# 03_-_Keyboard_Matrix_1.net
KiCad netlist of a schematic drawn in Altium Designer
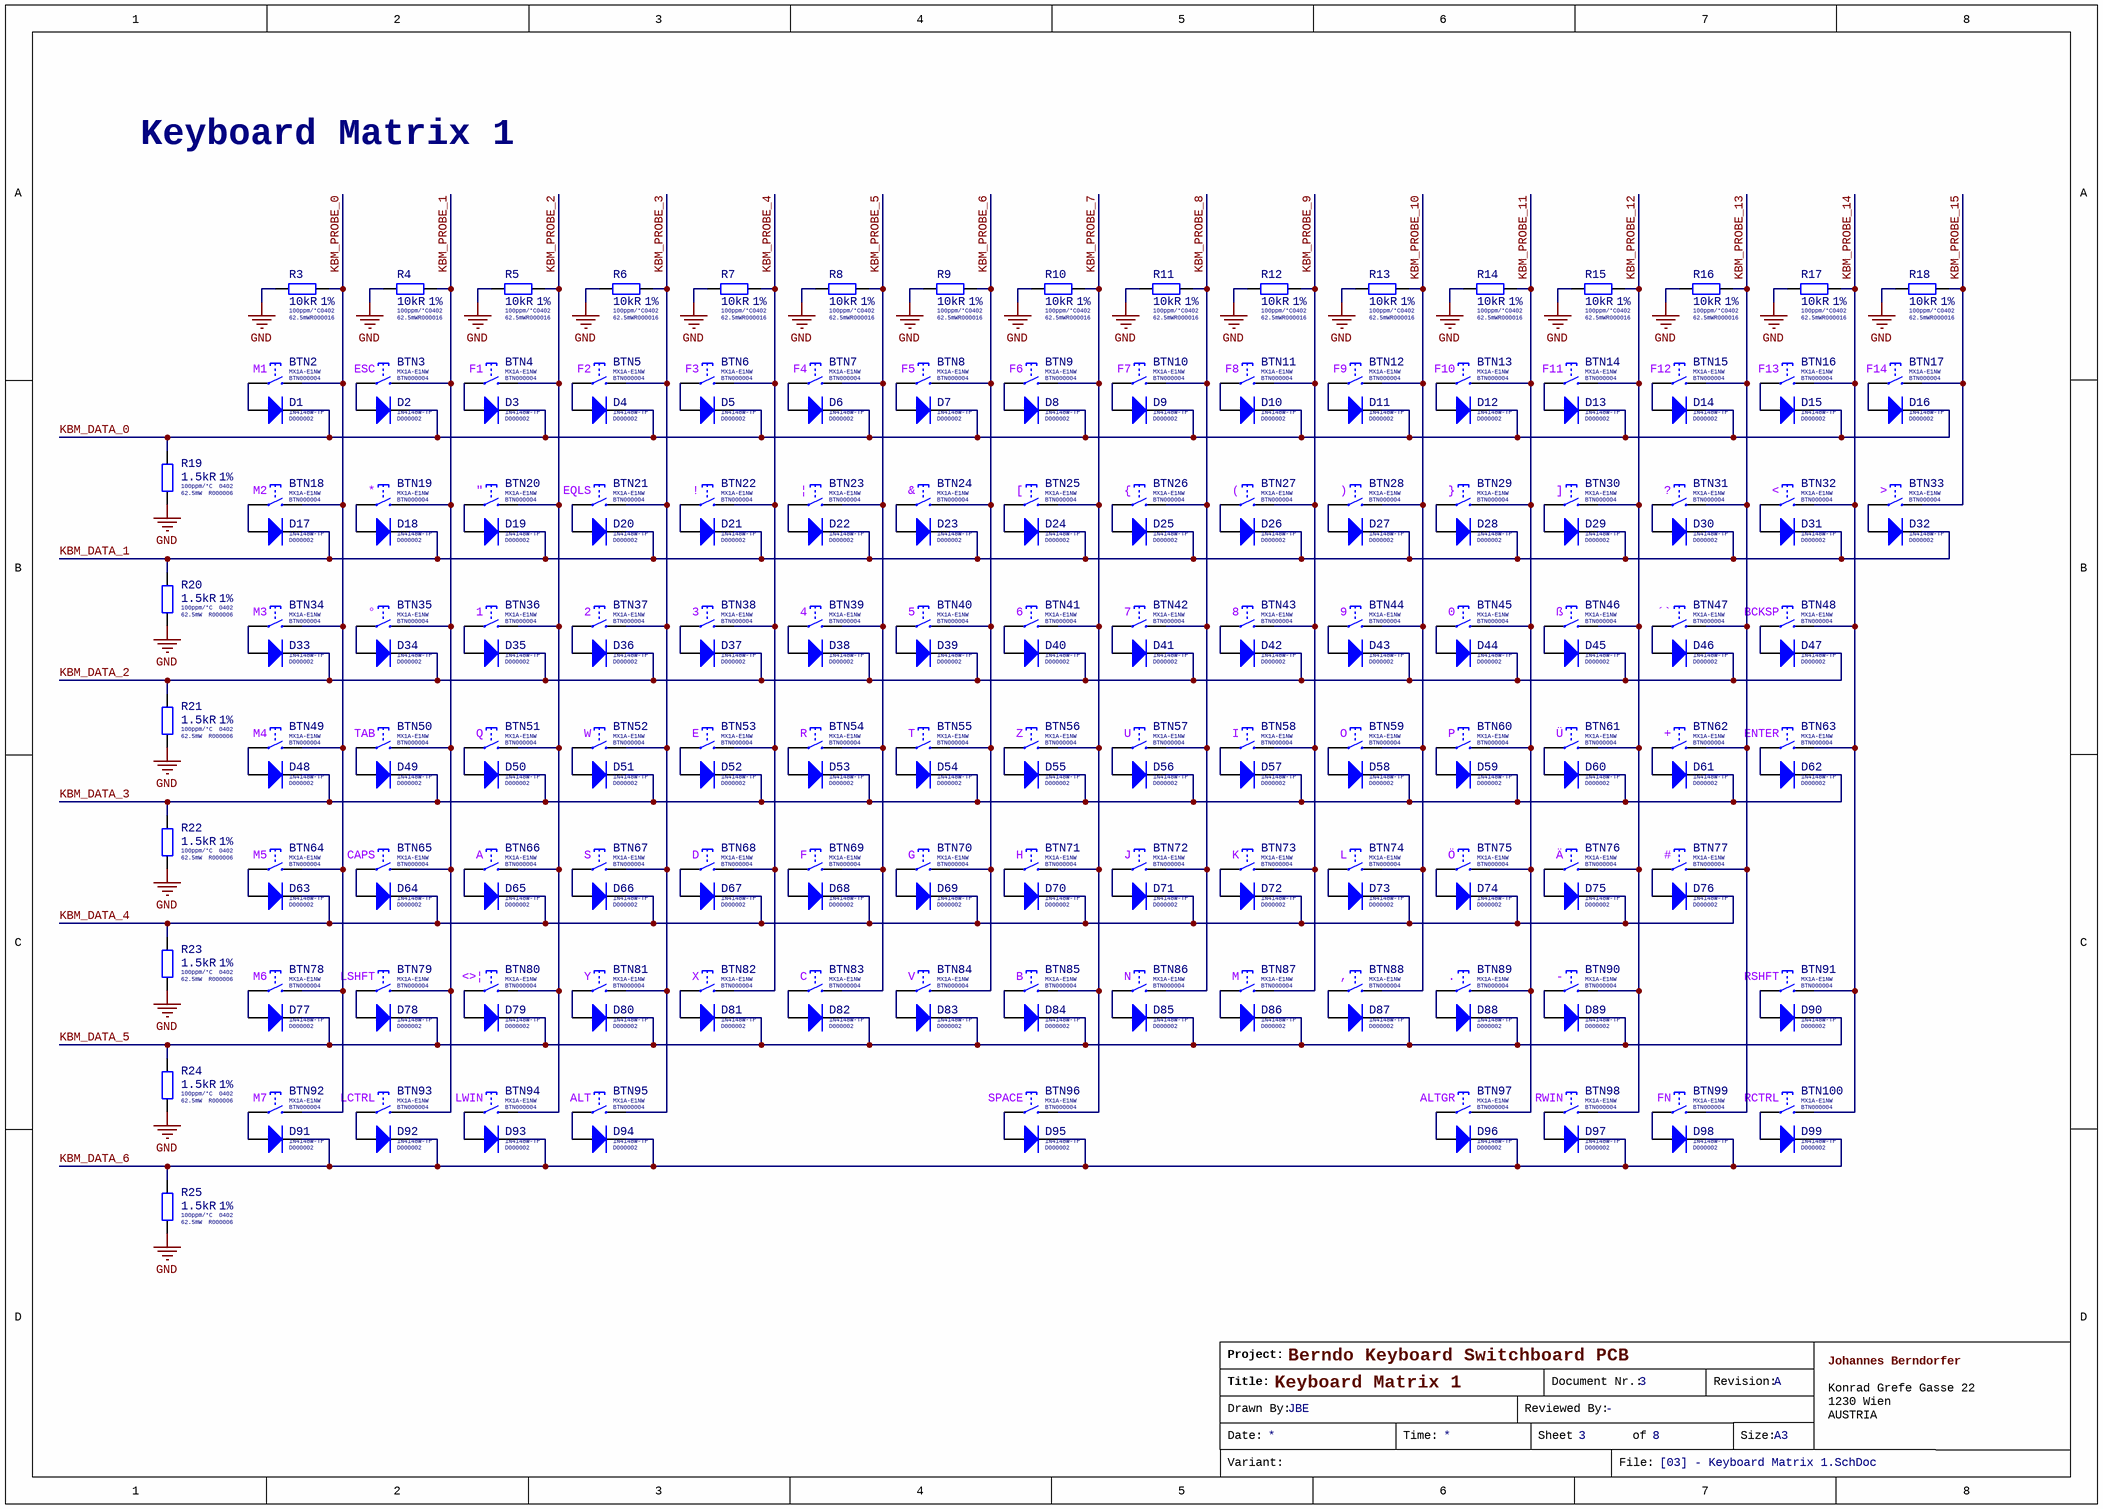
[diagram p0: [03] - Keyboard Matrix 1.SchDoc]

(export (version "E")
  (design (tool "Eeschema 10.0.6"))
  (components
    (comp (ref "BTN2")
      (value "MX1A-E1NW")
      (footprint "BTN-THT-MX-CHERRY")
      (description "BTN CHERRY MX BLUE SPST-NO 12V 10mA")
      (fields
        (field (name "MANUFACTURER") "Cherry")
        (field (name "INTERNAL PART NUMBER") "BTN000004")
        (field (name "KEY FUNCTION") "M1")
      )
      (libsource (lib "Altium_Lib_Standard") (part "MX1A-E1NW"))
    )
    (comp (ref "BTN3")
      (value "MX1A-E1NW")
      (footprint "BTN-THT-MX-CHERRY")
      (description "BTN CHERRY MX BLUE SPST-NO 12V 10mA")
      (fields
        (field (name "MANUFACTURER") "Cherry")
        (field (name "INTERNAL PART NUMBER") "BTN000004")
        (field (name "KEY FUNCTION") "ESC")
      )
      (libsource (lib "Altium_Lib_Standard") (part "MX1A-E1NW"))
    )
    (comp (ref "BTN4")
      (value "MX1A-E1NW")
      (footprint "BTN-THT-MX-CHERRY")
      (description "BTN CHERRY MX BLUE SPST-NO 12V 10mA")
      (fields
        (field (name "MANUFACTURER") "Cherry")
        (field (name "INTERNAL PART NUMBER") "BTN000004")
        (field (name "KEY FUNCTION") "F1")
      )
      (libsource (lib "Altium_Lib_Standard") (part "MX1A-E1NW"))
    )
    (comp (ref "BTN5")
      (value "MX1A-E1NW")
      (footprint "BTN-THT-MX-CHERRY")
      (description "BTN CHERRY MX BLUE SPST-NO 12V 10mA")
      (fields
        (field (name "MANUFACTURER") "Cherry")
        (field (name "INTERNAL PART NUMBER") "BTN000004")
        (field (name "KEY FUNCTION") "F2")
      )
      (libsource (lib "Altium_Lib_Standard") (part "MX1A-E1NW"))
    )
    (comp (ref "BTN6")
      (value "MX1A-E1NW")
      (footprint "BTN-THT-MX-CHERRY")
      (description "BTN CHERRY MX BLUE SPST-NO 12V 10mA")
      (fields
        (field (name "MANUFACTURER") "Cherry")
        (field (name "INTERNAL PART NUMBER") "BTN000004")
        (field (name "KEY FUNCTION") "F3")
      )
      (libsource (lib "Altium_Lib_Standard") (part "MX1A-E1NW"))
    )
    (comp (ref "BTN7")
      (value "MX1A-E1NW")
      (footprint "BTN-THT-MX-CHERRY")
      (description "BTN CHERRY MX BLUE SPST-NO 12V 10mA")
      (fields
        (field (name "MANUFACTURER") "Cherry")
        (field (name "INTERNAL PART NUMBER") "BTN000004")
        (field (name "KEY FUNCTION") "F4")
      )
      (libsource (lib "Altium_Lib_Standard") (part "MX1A-E1NW"))
    )
    (comp (ref "BTN8")
      (value "MX1A-E1NW")
      (footprint "BTN-THT-MX-CHERRY")
      (description "BTN CHERRY MX BLUE SPST-NO 12V 10mA")
      (fields
        (field (name "MANUFACTURER") "Cherry")
        (field (name "INTERNAL PART NUMBER") "BTN000004")
        (field (name "KEY FUNCTION") "F5")
      )
      (libsource (lib "Altium_Lib_Standard") (part "MX1A-E1NW"))
    )
    (comp (ref "BTN9")
      (value "MX1A-E1NW")
      (footprint "BTN-THT-MX-CHERRY")
      (description "BTN CHERRY MX BLUE SPST-NO 12V 10mA")
      (fields
        (field (name "MANUFACTURER") "Cherry")
        (field (name "INTERNAL PART NUMBER") "BTN000004")
        (field (name "KEY FUNCTION") "F6")
      )
      (libsource (lib "Altium_Lib_Standard") (part "MX1A-E1NW"))
    )
    (comp (ref "BTN10")
      (value "MX1A-E1NW")
      (footprint "BTN-THT-MX-CHERRY")
      (description "BTN CHERRY MX BLUE SPST-NO 12V 10mA")
      (fields
        (field (name "MANUFACTURER") "Cherry")
        (field (name "INTERNAL PART NUMBER") "BTN000004")
        (field (name "KEY FUNCTION") "F7")
      )
      (libsource (lib "Altium_Lib_Standard") (part "MX1A-E1NW"))
    )
    (comp (ref "BTN11")
      (value "MX1A-E1NW")
      (footprint "BTN-THT-MX-CHERRY")
      (description "BTN CHERRY MX BLUE SPST-NO 12V 10mA")
      (fields
        (field (name "MANUFACTURER") "Cherry")
        (field (name "INTERNAL PART NUMBER") "BTN000004")
        (field (name "KEY FUNCTION") "F8")
      )
      (libsource (lib "Altium_Lib_Standard") (part "MX1A-E1NW"))
    )
    (comp (ref "BTN12")
      (value "MX1A-E1NW")
      (footprint "BTN-THT-MX-CHERRY")
      (description "BTN CHERRY MX BLUE SPST-NO 12V 10mA")
      (fields
        (field (name "MANUFACTURER") "Cherry")
        (field (name "INTERNAL PART NUMBER") "BTN000004")
        (field (name "KEY FUNCTION") "F9")
      )
      (libsource (lib "Altium_Lib_Standard") (part "MX1A-E1NW"))
    )
    (comp (ref "BTN13")
      (value "MX1A-E1NW")
      (footprint "BTN-THT-MX-CHERRY")
      (description "BTN CHERRY MX BLUE SPST-NO 12V 10mA")
      (fields
        (field (name "MANUFACTURER") "Cherry")
        (field (name "INTERNAL PART NUMBER") "BTN000004")
        (field (name "KEY FUNCTION") "F10")
      )
      (libsource (lib "Altium_Lib_Standard") (part "MX1A-E1NW"))
    )
    (comp (ref "BTN14")
      (value "MX1A-E1NW")
      (footprint "BTN-THT-MX-CHERRY")
      (description "BTN CHERRY MX BLUE SPST-NO 12V 10mA")
      (fields
        (field (name "MANUFACTURER") "Cherry")
        (field (name "INTERNAL PART NUMBER") "BTN000004")
        (field (name "KEY FUNCTION") "F11")
      )
      (libsource (lib "Altium_Lib_Standard") (part "MX1A-E1NW"))
    )
    (comp (ref "BTN15")
      (value "MX1A-E1NW")
      (footprint "BTN-THT-MX-CHERRY")
      (description "BTN CHERRY MX BLUE SPST-NO 12V 10mA")
      (fields
        (field (name "MANUFACTURER") "Cherry")
        (field (name "INTERNAL PART NUMBER") "BTN000004")
        (field (name "KEY FUNCTION") "F12")
      )
      (libsource (lib "Altium_Lib_Standard") (part "MX1A-E1NW"))
    )
    (comp (ref "BTN16")
      (value "MX1A-E1NW")
      (footprint "BTN-THT-MX-CHERRY")
      (description "BTN CHERRY MX BLUE SPST-NO 12V 10mA")
      (fields
        (field (name "MANUFACTURER") "Cherry")
        (field (name "INTERNAL PART NUMBER") "BTN000004")
        (field (name "KEY FUNCTION") "F13")
      )
      (libsource (lib "Altium_Lib_Standard") (part "MX1A-E1NW"))
    )
    (comp (ref "BTN17")
      (value "MX1A-E1NW")
      (footprint "BTN-THT-MX-CHERRY")
      (description "BTN CHERRY MX BLUE SPST-NO 12V 10mA")
      (fields
        (field (name "MANUFACTURER") "Cherry")
        (field (name "INTERNAL PART NUMBER") "BTN000004")
        (field (name "KEY FUNCTION") "F14")
      )
      (libsource (lib "Altium_Lib_Standard") (part "MX1A-E1NW"))
    )
    (comp (ref "BTN18")
      (value "MX1A-E1NW")
      (footprint "BTN-THT-MX-CHERRY")
      (description "BTN CHERRY MX BLUE SPST-NO 12V 10mA")
      (fields
        (field (name "MANUFACTURER") "Cherry")
        (field (name "INTERNAL PART NUMBER") "BTN000004")
        (field (name "KEY FUNCTION") "M2")
      )
      (libsource (lib "Altium_Lib_Standard") (part "MX1A-E1NW"))
    )
    (comp (ref "BTN19")
      (value "MX1A-E1NW")
      (footprint "BTN-THT-MX-CHERRY")
      (description "BTN CHERRY MX BLUE SPST-NO 12V 10mA")
      (fields
        (field (name "MANUFACTURER") "Cherry")
        (field (name "INTERNAL PART NUMBER") "BTN000004")
        (field (name "KEY FUNCTION") "*")
      )
      (libsource (lib "Altium_Lib_Standard") (part "MX1A-E1NW"))
    )
    (comp (ref "BTN20")
      (value "MX1A-E1NW")
      (footprint "BTN-THT-MX-CHERRY")
      (description "BTN CHERRY MX BLUE SPST-NO 12V 10mA")
      (fields
        (field (name "MANUFACTURER") "Cherry")
        (field (name "INTERNAL PART NUMBER") "BTN000004")
        (field (name "KEY FUNCTION") "\"")
      )
      (libsource (lib "Altium_Lib_Standard") (part "MX1A-E1NW"))
    )
    (comp (ref "BTN21")
      (value "MX1A-E1NW")
      (footprint "BTN-THT-MX-CHERRY")
      (description "BTN CHERRY MX BLUE SPST-NO 12V 10mA")
      (fields
        (field (name "MANUFACTURER") "Cherry")
        (field (name "INTERNAL PART NUMBER") "BTN000004")
        (field (name "KEY FUNCTION") "EQLS")
      )
      (libsource (lib "Altium_Lib_Standard") (part "MX1A-E1NW"))
    )
    (comp (ref "BTN22")
      (value "MX1A-E1NW")
      (footprint "BTN-THT-MX-CHERRY")
      (description "BTN CHERRY MX BLUE SPST-NO 12V 10mA")
      (fields
        (field (name "MANUFACTURER") "Cherry")
        (field (name "INTERNAL PART NUMBER") "BTN000004")
        (field (name "KEY FUNCTION") "!")
      )
      (libsource (lib "Altium_Lib_Standard") (part "MX1A-E1NW"))
    )
    (comp (ref "BTN23")
      (value "MX1A-E1NW")
      (footprint "BTN-THT-MX-CHERRY")
      (description "BTN CHERRY MX BLUE SPST-NO 12V 10mA")
      (fields
        (field (name "MANUFACTURER") "Cherry")
        (field (name "INTERNAL PART NUMBER") "BTN000004")
        (field (name "KEY FUNCTION") "¦")
      )
      (libsource (lib "Altium_Lib_Standard") (part "MX1A-E1NW"))
    )
    (comp (ref "BTN24")
      (value "MX1A-E1NW")
      (footprint "BTN-THT-MX-CHERRY")
      (description "BTN CHERRY MX BLUE SPST-NO 12V 10mA")
      (fields
        (field (name "MANUFACTURER") "Cherry")
        (field (name "INTERNAL PART NUMBER") "BTN000004")
        (field (name "KEY FUNCTION") "&")
      )
      (libsource (lib "Altium_Lib_Standard") (part "MX1A-E1NW"))
    )
    (comp (ref "BTN25")
      (value "MX1A-E1NW")
      (footprint "BTN-THT-MX-CHERRY")
      (description "BTN CHERRY MX BLUE SPST-NO 12V 10mA")
      (fields
        (field (name "MANUFACTURER") "Cherry")
        (field (name "INTERNAL PART NUMBER") "BTN000004")
        (field (name "KEY FUNCTION") "[")
      )
      (libsource (lib "Altium_Lib_Standard") (part "MX1A-E1NW"))
    )
    (comp (ref "BTN26")
      (value "MX1A-E1NW")
      (footprint "BTN-THT-MX-CHERRY")
      (description "BTN CHERRY MX BLUE SPST-NO 12V 10mA")
      (fields
        (field (name "MANUFACTURER") "Cherry")
        (field (name "INTERNAL PART NUMBER") "BTN000004")
        (field (name "KEY FUNCTION") "{")
      )
      (libsource (lib "Altium_Lib_Standard") (part "MX1A-E1NW"))
    )
    (comp (ref "BTN27")
      (value "MX1A-E1NW")
      (footprint "BTN-THT-MX-CHERRY")
      (description "BTN CHERRY MX BLUE SPST-NO 12V 10mA")
      (fields
        (field (name "MANUFACTURER") "Cherry")
        (field (name "INTERNAL PART NUMBER") "BTN000004")
        (field (name "KEY FUNCTION") "(")
      )
      (libsource (lib "Altium_Lib_Standard") (part "MX1A-E1NW"))
    )
    (comp (ref "BTN28")
      (value "MX1A-E1NW")
      (footprint "BTN-THT-MX-CHERRY")
      (description "BTN CHERRY MX BLUE SPST-NO 12V 10mA")
      (fields
        (field (name "MANUFACTURER") "Cherry")
        (field (name "INTERNAL PART NUMBER") "BTN000004")
        (field (name "KEY FUNCTION") ")")
      )
      (libsource (lib "Altium_Lib_Standard") (part "MX1A-E1NW"))
    )
    (comp (ref "BTN29")
      (value "MX1A-E1NW")
      (footprint "BTN-THT-MX-CHERRY")
      (description "BTN CHERRY MX BLUE SPST-NO 12V 10mA")
      (fields
        (field (name "MANUFACTURER") "Cherry")
        (field (name "INTERNAL PART NUMBER") "BTN000004")
        (field (name "KEY FUNCTION") "}")
      )
      (libsource (lib "Altium_Lib_Standard") (part "MX1A-E1NW"))
    )
    (comp (ref "BTN30")
      (value "MX1A-E1NW")
      (footprint "BTN-THT-MX-CHERRY")
      (description "BTN CHERRY MX BLUE SPST-NO 12V 10mA")
      (fields
        (field (name "MANUFACTURER") "Cherry")
        (field (name "INTERNAL PART NUMBER") "BTN000004")
        (field (name "KEY FUNCTION") "]")
      )
      (libsource (lib "Altium_Lib_Standard") (part "MX1A-E1NW"))
    )
    (comp (ref "BTN31")
      (value "MX1A-E1NW")
      (footprint "BTN-THT-MX-CHERRY")
      (description "BTN CHERRY MX BLUE SPST-NO 12V 10mA")
      (fields
        (field (name "MANUFACTURER") "Cherry")
        (field (name "INTERNAL PART NUMBER") "BTN000004")
        (field (name "KEY FUNCTION") "?")
      )
      (libsource (lib "Altium_Lib_Standard") (part "MX1A-E1NW"))
    )
    (comp (ref "BTN32")
      (value "MX1A-E1NW")
      (footprint "BTN-THT-MX-CHERRY")
      (description "BTN CHERRY MX BLUE SPST-NO 12V 10mA")
      (fields
        (field (name "MANUFACTURER") "Cherry")
        (field (name "INTERNAL PART NUMBER") "BTN000004")
        (field (name "KEY FUNCTION") "<")
      )
      (libsource (lib "Altium_Lib_Standard") (part "MX1A-E1NW"))
    )
    (comp (ref "BTN33")
      (value "MX1A-E1NW")
      (footprint "BTN-THT-MX-CHERRY")
      (description "BTN CHERRY MX BLUE SPST-NO 12V 10mA")
      (fields
        (field (name "MANUFACTURER") "Cherry")
        (field (name "INTERNAL PART NUMBER") "BTN000004")
        (field (name "KEY FUNCTION") ">")
      )
      (libsource (lib "Altium_Lib_Standard") (part "MX1A-E1NW"))
    )
    (comp (ref "BTN34")
      (value "MX1A-E1NW")
      (footprint "BTN-THT-MX-CHERRY")
      (description "BTN CHERRY MX BLUE SPST-NO 12V 10mA")
      (fields
        (field (name "MANUFACTURER") "Cherry")
        (field (name "INTERNAL PART NUMBER") "BTN000004")
        (field (name "KEY FUNCTION") "M3")
      )
      (libsource (lib "Altium_Lib_Standard") (part "MX1A-E1NW"))
    )
    (comp (ref "BTN35")
      (value "MX1A-E1NW")
      (footprint "BTN-THT-MX-CHERRY")
      (description "BTN CHERRY MX BLUE SPST-NO 12V 10mA")
      (fields
        (field (name "MANUFACTURER") "Cherry")
        (field (name "INTERNAL PART NUMBER") "BTN000004")
        (field (name "KEY FUNCTION") "°")
      )
      (libsource (lib "Altium_Lib_Standard") (part "MX1A-E1NW"))
    )
    (comp (ref "BTN36")
      (value "MX1A-E1NW")
      (footprint "BTN-THT-MX-CHERRY")
      (description "BTN CHERRY MX BLUE SPST-NO 12V 10mA")
      (fields
        (field (name "MANUFACTURER") "Cherry")
        (field (name "INTERNAL PART NUMBER") "BTN000004")
        (field (name "KEY FUNCTION") "1")
      )
      (libsource (lib "Altium_Lib_Standard") (part "MX1A-E1NW"))
    )
    (comp (ref "BTN37")
      (value "MX1A-E1NW")
      (footprint "BTN-THT-MX-CHERRY")
      (description "BTN CHERRY MX BLUE SPST-NO 12V 10mA")
      (fields
        (field (name "MANUFACTURER") "Cherry")
        (field (name "INTERNAL PART NUMBER") "BTN000004")
        (field (name "KEY FUNCTION") "2")
      )
      (libsource (lib "Altium_Lib_Standard") (part "MX1A-E1NW"))
    )
    (comp (ref "BTN38")
      (value "MX1A-E1NW")
      (footprint "BTN-THT-MX-CHERRY")
      (description "BTN CHERRY MX BLUE SPST-NO 12V 10mA")
      (fields
        (field (name "MANUFACTURER") "Cherry")
        (field (name "INTERNAL PART NUMBER") "BTN000004")
        (field (name "KEY FUNCTION") "3")
      )
      (libsource (lib "Altium_Lib_Standard") (part "MX1A-E1NW"))
    )
    (comp (ref "BTN39")
      (value "MX1A-E1NW")
      (footprint "BTN-THT-MX-CHERRY")
      (description "BTN CHERRY MX BLUE SPST-NO 12V 10mA")
      (fields
        (field (name "MANUFACTURER") "Cherry")
        (field (name "INTERNAL PART NUMBER") "BTN000004")
        (field (name "KEY FUNCTION") "4")
      )
      (libsource (lib "Altium_Lib_Standard") (part "MX1A-E1NW"))
    )
    (comp (ref "BTN40")
      (value "MX1A-E1NW")
      (footprint "BTN-THT-MX-CHERRY")
      (description "BTN CHERRY MX BLUE SPST-NO 12V 10mA")
      (fields
        (field (name "MANUFACTURER") "Cherry")
        (field (name "INTERNAL PART NUMBER") "BTN000004")
        (field (name "KEY FUNCTION") "5")
      )
      (libsource (lib "Altium_Lib_Standard") (part "MX1A-E1NW"))
    )
    (comp (ref "BTN41")
      (value "MX1A-E1NW")
      (footprint "BTN-THT-MX-CHERRY")
      (description "BTN CHERRY MX BLUE SPST-NO 12V 10mA")
      (fields
        (field (name "MANUFACTURER") "Cherry")
        (field (name "INTERNAL PART NUMBER") "BTN000004")
        (field (name "KEY FUNCTION") "6")
      )
      (libsource (lib "Altium_Lib_Standard") (part "MX1A-E1NW"))
    )
    (comp (ref "BTN42")
      (value "MX1A-E1NW")
      (footprint "BTN-THT-MX-CHERRY")
      (description "BTN CHERRY MX BLUE SPST-NO 12V 10mA")
      (fields
        (field (name "MANUFACTURER") "Cherry")
        (field (name "INTERNAL PART NUMBER") "BTN000004")
        (field (name "KEY FUNCTION") "7")
      )
      (libsource (lib "Altium_Lib_Standard") (part "MX1A-E1NW"))
    )
    (comp (ref "BTN43")
      (value "MX1A-E1NW")
      (footprint "BTN-THT-MX-CHERRY")
      (description "BTN CHERRY MX BLUE SPST-NO 12V 10mA")
      (fields
        (field (name "MANUFACTURER") "Cherry")
        (field (name "INTERNAL PART NUMBER") "BTN000004")
        (field (name "KEY FUNCTION") "8")
      )
      (libsource (lib "Altium_Lib_Standard") (part "MX1A-E1NW"))
    )
    (comp (ref "BTN44")
      (value "MX1A-E1NW")
      (footprint "BTN-THT-MX-CHERRY")
      (description "BTN CHERRY MX BLUE SPST-NO 12V 10mA")
      (fields
        (field (name "MANUFACTURER") "Cherry")
        (field (name "INTERNAL PART NUMBER") "BTN000004")
        (field (name "KEY FUNCTION") "9")
      )
      (libsource (lib "Altium_Lib_Standard") (part "MX1A-E1NW"))
    )
    (comp (ref "BTN45")
      (value "MX1A-E1NW")
      (footprint "BTN-THT-MX-CHERRY")
      (description "BTN CHERRY MX BLUE SPST-NO 12V 10mA")
      (fields
        (field (name "MANUFACTURER") "Cherry")
        (field (name "INTERNAL PART NUMBER") "BTN000004")
        (field (name "KEY FUNCTION") "0")
      )
      (libsource (lib "Altium_Lib_Standard") (part "MX1A-E1NW"))
    )
    (comp (ref "BTN46")
      (value "MX1A-E1NW")
      (footprint "BTN-THT-MX-CHERRY")
      (description "BTN CHERRY MX BLUE SPST-NO 12V 10mA")
      (fields
        (field (name "MANUFACTURER") "Cherry")
        (field (name "INTERNAL PART NUMBER") "BTN000004")
        (field (name "KEY FUNCTION") "ß")
      )
      (libsource (lib "Altium_Lib_Standard") (part "MX1A-E1NW"))
    )
    (comp (ref "BTN47")
      (value "MX1A-E1NW")
      (footprint "BTN-THT-MX-CHERRY")
      (description "BTN CHERRY MX BLUE SPST-NO 12V 10mA")
      (fields
        (field (name "MANUFACTURER") "Cherry")
        (field (name "INTERNAL PART NUMBER") "BTN000004")
        (field (name "KEY FUNCTION") "´`")
      )
      (libsource (lib "Altium_Lib_Standard") (part "MX1A-E1NW"))
    )
    (comp (ref "BTN48")
      (value "MX1A-E1NW")
      (footprint "BTN-THT-MX-CHERRY")
      (description "BTN CHERRY MX BLUE SPST-NO 12V 10mA")
      (fields
        (field (name "MANUFACTURER") "Cherry")
        (field (name "INTERNAL PART NUMBER") "BTN000004")
        (field (name "KEY FUNCTION") "BCKSP")
      )
      (libsource (lib "Altium_Lib_Standard") (part "MX1A-E1NW"))
    )
    (comp (ref "BTN49")
      (value "MX1A-E1NW")
      (footprint "BTN-THT-MX-CHERRY")
      (description "BTN CHERRY MX BLUE SPST-NO 12V 10mA")
      (fields
        (field (name "MANUFACTURER") "Cherry")
        (field (name "INTERNAL PART NUMBER") "BTN000004")
        (field (name "KEY FUNCTION") "M4")
      )
      (libsource (lib "Altium_Lib_Standard") (part "MX1A-E1NW"))
    )
    (comp (ref "BTN50")
      (value "MX1A-E1NW")
      (footprint "BTN-THT-MX-CHERRY")
      (description "BTN CHERRY MX BLUE SPST-NO 12V 10mA")
      (fields
        (field (name "MANUFACTURER") "Cherry")
        (field (name "INTERNAL PART NUMBER") "BTN000004")
        (field (name "KEY FUNCTION") "TAB")
      )
      (libsource (lib "Altium_Lib_Standard") (part "MX1A-E1NW"))
    )
    (comp (ref "BTN51")
      (value "MX1A-E1NW")
      (footprint "BTN-THT-MX-CHERRY")
      (description "BTN CHERRY MX BLUE SPST-NO 12V 10mA")
      (fields
        (field (name "MANUFACTURER") "Cherry")
        (field (name "INTERNAL PART NUMBER") "BTN000004")
        (field (name "KEY FUNCTION") "Q")
      )
      (libsource (lib "Altium_Lib_Standard") (part "MX1A-E1NW"))
    )
    (comp (ref "BTN52")
      (value "MX1A-E1NW")
      (footprint "BTN-THT-MX-CHERRY")
      (description "BTN CHERRY MX BLUE SPST-NO 12V 10mA")
      (fields
        (field (name "MANUFACTURER") "Cherry")
        (field (name "INTERNAL PART NUMBER") "BTN000004")
        (field (name "KEY FUNCTION") "W")
      )
      (libsource (lib "Altium_Lib_Standard") (part "MX1A-E1NW"))
    )
    (comp (ref "BTN53")
      (value "MX1A-E1NW")
      (footprint "BTN-THT-MX-CHERRY")
      (description "BTN CHERRY MX BLUE SPST-NO 12V 10mA")
      (fields
        (field (name "MANUFACTURER") "Cherry")
        (field (name "INTERNAL PART NUMBER") "BTN000004")
        (field (name "KEY FUNCTION") "E")
      )
      (libsource (lib "Altium_Lib_Standard") (part "MX1A-E1NW"))
    )
    (comp (ref "BTN54")
      (value "MX1A-E1NW")
      (footprint "BTN-THT-MX-CHERRY")
      (description "BTN CHERRY MX BLUE SPST-NO 12V 10mA")
      (fields
        (field (name "MANUFACTURER") "Cherry")
        (field (name "INTERNAL PART NUMBER") "BTN000004")
        (field (name "KEY FUNCTION") "R")
      )
      (libsource (lib "Altium_Lib_Standard") (part "MX1A-E1NW"))
    )
    (comp (ref "BTN55")
      (value "MX1A-E1NW")
      (footprint "BTN-THT-MX-CHERRY")
      (description "BTN CHERRY MX BLUE SPST-NO 12V 10mA")
      (fields
        (field (name "MANUFACTURER") "Cherry")
        (field (name "INTERNAL PART NUMBER") "BTN000004")
        (field (name "KEY FUNCTION") "T")
      )
      (libsource (lib "Altium_Lib_Standard") (part "MX1A-E1NW"))
    )
    (comp (ref "BTN56")
      (value "MX1A-E1NW")
      (footprint "BTN-THT-MX-CHERRY")
      (description "BTN CHERRY MX BLUE SPST-NO 12V 10mA")
      (fields
        (field (name "MANUFACTURER") "Cherry")
        (field (name "INTERNAL PART NUMBER") "BTN000004")
        (field (name "KEY FUNCTION") "Z")
      )
      (libsource (lib "Altium_Lib_Standard") (part "MX1A-E1NW"))
    )
    (comp (ref "BTN57")
      (value "MX1A-E1NW")
      (footprint "BTN-THT-MX-CHERRY")
      (description "BTN CHERRY MX BLUE SPST-NO 12V 10mA")
      (fields
        (field (name "MANUFACTURER") "Cherry")
        (field (name "INTERNAL PART NUMBER") "BTN000004")
        (field (name "KEY FUNCTION") "U")
      )
      (libsource (lib "Altium_Lib_Standard") (part "MX1A-E1NW"))
    )
    (comp (ref "BTN58")
      (value "MX1A-E1NW")
      (footprint "BTN-THT-MX-CHERRY")
      (description "BTN CHERRY MX BLUE SPST-NO 12V 10mA")
      (fields
        (field (name "MANUFACTURER") "Cherry")
        (field (name "INTERNAL PART NUMBER") "BTN000004")
        (field (name "KEY FUNCTION") "I")
      )
      (libsource (lib "Altium_Lib_Standard") (part "MX1A-E1NW"))
    )
    (comp (ref "BTN59")
      (value "MX1A-E1NW")
      (footprint "BTN-THT-MX-CHERRY")
      (description "BTN CHERRY MX BLUE SPST-NO 12V 10mA")
      (fields
        (field (name "MANUFACTURER") "Cherry")
        (field (name "INTERNAL PART NUMBER") "BTN000004")
        (field (name "KEY FUNCTION") "O")
      )
      (libsource (lib "Altium_Lib_Standard") (part "MX1A-E1NW"))
    )
    (comp (ref "BTN60")
      (value "MX1A-E1NW")
      (footprint "BTN-THT-MX-CHERRY")
      (description "BTN CHERRY MX BLUE SPST-NO 12V 10mA")
      (fields
        (field (name "MANUFACTURER") "Cherry")
        (field (name "INTERNAL PART NUMBER") "BTN000004")
        (field (name "KEY FUNCTION") "P")
      )
      (libsource (lib "Altium_Lib_Standard") (part "MX1A-E1NW"))
    )
    (comp (ref "BTN61")
      (value "MX1A-E1NW")
      (footprint "BTN-THT-MX-CHERRY")
      (description "BTN CHERRY MX BLUE SPST-NO 12V 10mA")
      (fields
        (field (name "MANUFACTURER") "Cherry")
        (field (name "INTERNAL PART NUMBER") "BTN000004")
        (field (name "KEY FUNCTION") "Ü")
      )
      (libsource (lib "Altium_Lib_Standard") (part "MX1A-E1NW"))
    )
    (comp (ref "BTN62")
      (value "MX1A-E1NW")
      (footprint "BTN-THT-MX-CHERRY")
      (description "BTN CHERRY MX BLUE SPST-NO 12V 10mA")
      (fields
        (field (name "MANUFACTURER") "Cherry")
        (field (name "INTERNAL PART NUMBER") "BTN000004")
        (field (name "KEY FUNCTION") "+")
      )
      (libsource (lib "Altium_Lib_Standard") (part "MX1A-E1NW"))
    )
    (comp (ref "BTN63")
      (value "MX1A-E1NW")
      (footprint "BTN-THT-MX-CHERRY")
      (description "BTN CHERRY MX BLUE SPST-NO 12V 10mA")
      (fields
        (field (name "MANUFACTURER") "Cherry")
        (field (name "INTERNAL PART NUMBER") "BTN000004")
        (field (name "KEY FUNCTION") "ENTER")
      )
      (libsource (lib "Altium_Lib_Standard") (part "MX1A-E1NW"))
    )
    (comp (ref "BTN64")
      (value "MX1A-E1NW")
      (footprint "BTN-THT-MX-CHERRY")
      (description "BTN CHERRY MX BLUE SPST-NO 12V 10mA")
      (fields
        (field (name "MANUFACTURER") "Cherry")
        (field (name "INTERNAL PART NUMBER") "BTN000004")
        (field (name "KEY FUNCTION") "M5")
      )
      (libsource (lib "Altium_Lib_Standard") (part "MX1A-E1NW"))
    )
    (comp (ref "BTN65")
      (value "MX1A-E1NW")
      (footprint "BTN-THT-MX-CHERRY")
      (description "BTN CHERRY MX BLUE SPST-NO 12V 10mA")
      (fields
        (field (name "MANUFACTURER") "Cherry")
        (field (name "INTERNAL PART NUMBER") "BTN000004")
        (field (name "KEY FUNCTION") "CAPS")
      )
      (libsource (lib "Altium_Lib_Standard") (part "MX1A-E1NW"))
    )
    (comp (ref "BTN66")
      (value "MX1A-E1NW")
      (footprint "BTN-THT-MX-CHERRY")
      (description "BTN CHERRY MX BLUE SPST-NO 12V 10mA")
      (fields
        (field (name "MANUFACTURER") "Cherry")
        (field (name "INTERNAL PART NUMBER") "BTN000004")
        (field (name "KEY FUNCTION") "A")
      )
      (libsource (lib "Altium_Lib_Standard") (part "MX1A-E1NW"))
    )
    (comp (ref "BTN67")
      (value "MX1A-E1NW")
      (footprint "BTN-THT-MX-CHERRY")
      (description "BTN CHERRY MX BLUE SPST-NO 12V 10mA")
      (fields
        (field (name "MANUFACTURER") "Cherry")
        (field (name "INTERNAL PART NUMBER") "BTN000004")
        (field (name "KEY FUNCTION") "S")
      )
      (libsource (lib "Altium_Lib_Standard") (part "MX1A-E1NW"))
    )
    (comp (ref "BTN68")
      (value "MX1A-E1NW")
      (footprint "BTN-THT-MX-CHERRY")
      (description "BTN CHERRY MX BLUE SPST-NO 12V 10mA")
      (fields
        (field (name "MANUFACTURER") "Cherry")
        (field (name "INTERNAL PART NUMBER") "BTN000004")
        (field (name "KEY FUNCTION") "D")
      )
      (libsource (lib "Altium_Lib_Standard") (part "MX1A-E1NW"))
    )
    (comp (ref "BTN69")
      (value "MX1A-E1NW")
      (footprint "BTN-THT-MX-CHERRY")
      (description "BTN CHERRY MX BLUE SPST-NO 12V 10mA")
      (fields
        (field (name "MANUFACTURER") "Cherry")
        (field (name "INTERNAL PART NUMBER") "BTN000004")
        (field (name "KEY FUNCTION") "F")
      )
      (libsource (lib "Altium_Lib_Standard") (part "MX1A-E1NW"))
    )
    (comp (ref "BTN70")
      (value "MX1A-E1NW")
      (footprint "BTN-THT-MX-CHERRY")
      (description "BTN CHERRY MX BLUE SPST-NO 12V 10mA")
      (fields
        (field (name "MANUFACTURER") "Cherry")
        (field (name "INTERNAL PART NUMBER") "BTN000004")
        (field (name "KEY FUNCTION") "G")
      )
      (libsource (lib "Altium_Lib_Standard") (part "MX1A-E1NW"))
    )
    (comp (ref "BTN71")
      (value "MX1A-E1NW")
      (footprint "BTN-THT-MX-CHERRY")
      (description "BTN CHERRY MX BLUE SPST-NO 12V 10mA")
      (fields
        (field (name "MANUFACTURER") "Cherry")
        (field (name "INTERNAL PART NUMBER") "BTN000004")
        (field (name "KEY FUNCTION") "H")
      )
      (libsource (lib "Altium_Lib_Standard") (part "MX1A-E1NW"))
    )
    (comp (ref "BTN72")
      (value "MX1A-E1NW")
      (footprint "BTN-THT-MX-CHERRY")
      (description "BTN CHERRY MX BLUE SPST-NO 12V 10mA")
      (fields
        (field (name "MANUFACTURER") "Cherry")
        (field (name "INTERNAL PART NUMBER") "BTN000004")
        (field (name "KEY FUNCTION") "J")
      )
      (libsource (lib "Altium_Lib_Standard") (part "MX1A-E1NW"))
    )
    (comp (ref "BTN73")
      (value "MX1A-E1NW")
      (footprint "BTN-THT-MX-CHERRY")
      (description "BTN CHERRY MX BLUE SPST-NO 12V 10mA")
      (fields
        (field (name "MANUFACTURER") "Cherry")
        (field (name "INTERNAL PART NUMBER") "BTN000004")
        (field (name "KEY FUNCTION") "K")
      )
      (libsource (lib "Altium_Lib_Standard") (part "MX1A-E1NW"))
    )
    (comp (ref "BTN74")
      (value "MX1A-E1NW")
      (footprint "BTN-THT-MX-CHERRY")
      (description "BTN CHERRY MX BLUE SPST-NO 12V 10mA")
      (fields
        (field (name "MANUFACTURER") "Cherry")
        (field (name "INTERNAL PART NUMBER") "BTN000004")
        (field (name "KEY FUNCTION") "L")
      )
      (libsource (lib "Altium_Lib_Standard") (part "MX1A-E1NW"))
    )
    (comp (ref "BTN75")
      (value "MX1A-E1NW")
      (footprint "BTN-THT-MX-CHERRY")
      (description "BTN CHERRY MX BLUE SPST-NO 12V 10mA")
      (fields
        (field (name "MANUFACTURER") "Cherry")
        (field (name "INTERNAL PART NUMBER") "BTN000004")
        (field (name "KEY FUNCTION") "Ö")
      )
      (libsource (lib "Altium_Lib_Standard") (part "MX1A-E1NW"))
    )
    (comp (ref "BTN76")
      (value "MX1A-E1NW")
      (footprint "BTN-THT-MX-CHERRY")
      (description "BTN CHERRY MX BLUE SPST-NO 12V 10mA")
      (fields
        (field (name "MANUFACTURER") "Cherry")
        (field (name "INTERNAL PART NUMBER") "BTN000004")
        (field (name "KEY FUNCTION") "Ä")
      )
      (libsource (lib "Altium_Lib_Standard") (part "MX1A-E1NW"))
    )
    (comp (ref "BTN77")
      (value "MX1A-E1NW")
      (footprint "BTN-THT-MX-CHERRY")
      (description "BTN CHERRY MX BLUE SPST-NO 12V 10mA")
      (fields
        (field (name "MANUFACTURER") "Cherry")
        (field (name "INTERNAL PART NUMBER") "BTN000004")
        (field (name "KEY FUNCTION") "#")
      )
      (libsource (lib "Altium_Lib_Standard") (part "MX1A-E1NW"))
    )
    (comp (ref "BTN78")
      (value "MX1A-E1NW")
      (footprint "BTN-THT-MX-CHERRY")
      (description "BTN CHERRY MX BLUE SPST-NO 12V 10mA")
      (fields
        (field (name "MANUFACTURER") "Cherry")
        (field (name "INTERNAL PART NUMBER") "BTN000004")
        (field (name "KEY FUNCTION") "M6")
      )
      (libsource (lib "Altium_Lib_Standard") (part "MX1A-E1NW"))
    )
    (comp (ref "BTN79")
      (value "MX1A-E1NW")
      (footprint "BTN-THT-MX-CHERRY")
      (description "BTN CHERRY MX BLUE SPST-NO 12V 10mA")
      (fields
        (field (name "MANUFACTURER") "Cherry")
        (field (name "INTERNAL PART NUMBER") "BTN000004")
        (field (name "KEY FUNCTION") "LSHFT")
      )
      (libsource (lib "Altium_Lib_Standard") (part "MX1A-E1NW"))
    )
    (comp (ref "BTN80")
      (value "MX1A-E1NW")
      (footprint "BTN-THT-MX-CHERRY")
      (description "BTN CHERRY MX BLUE SPST-NO 12V 10mA")
      (fields
        (field (name "MANUFACTURER") "Cherry")
        (field (name "INTERNAL PART NUMBER") "BTN000004")
        (field (name "KEY FUNCTION") "<>¦")
      )
      (libsource (lib "Altium_Lib_Standard") (part "MX1A-E1NW"))
    )
    (comp (ref "BTN81")
      (value "MX1A-E1NW")
      (footprint "BTN-THT-MX-CHERRY")
      (description "BTN CHERRY MX BLUE SPST-NO 12V 10mA")
      (fields
        (field (name "MANUFACTURER") "Cherry")
        (field (name "INTERNAL PART NUMBER") "BTN000004")
        (field (name "KEY FUNCTION") "Y")
      )
      (libsource (lib "Altium_Lib_Standard") (part "MX1A-E1NW"))
    )
    (comp (ref "BTN82")
      (value "MX1A-E1NW")
      (footprint "BTN-THT-MX-CHERRY")
      (description "BTN CHERRY MX BLUE SPST-NO 12V 10mA")
      (fields
        (field (name "MANUFACTURER") "Cherry")
        (field (name "INTERNAL PART NUMBER") "BTN000004")
        (field (name "KEY FUNCTION") "X")
      )
      (libsource (lib "Altium_Lib_Standard") (part "MX1A-E1NW"))
    )
    (comp (ref "BTN83")
      (value "MX1A-E1NW")
      (footprint "BTN-THT-MX-CHERRY")
      (description "BTN CHERRY MX BLUE SPST-NO 12V 10mA")
      (fields
        (field (name "MANUFACTURER") "Cherry")
        (field (name "INTERNAL PART NUMBER") "BTN000004")
        (field (name "KEY FUNCTION") "C")
      )
      (libsource (lib "Altium_Lib_Standard") (part "MX1A-E1NW"))
    )
    (comp (ref "BTN84")
      (value "MX1A-E1NW")
      (footprint "BTN-THT-MX-CHERRY")
      (description "BTN CHERRY MX BLUE SPST-NO 12V 10mA")
      (fields
        (field (name "MANUFACTURER") "Cherry")
        (field (name "INTERNAL PART NUMBER") "BTN000004")
        (field (name "KEY FUNCTION") "V")
      )
      (libsource (lib "Altium_Lib_Standard") (part "MX1A-E1NW"))
    )
    (comp (ref "BTN85")
      (value "MX1A-E1NW")
      (footprint "BTN-THT-MX-CHERRY")
      (description "BTN CHERRY MX BLUE SPST-NO 12V 10mA")
      (fields
        (field (name "MANUFACTURER") "Cherry")
        (field (name "INTERNAL PART NUMBER") "BTN000004")
        (field (name "KEY FUNCTION") "B")
      )
      (libsource (lib "Altium_Lib_Standard") (part "MX1A-E1NW"))
    )
    (comp (ref "BTN86")
      (value "MX1A-E1NW")
      (footprint "BTN-THT-MX-CHERRY")
      (description "BTN CHERRY MX BLUE SPST-NO 12V 10mA")
      (fields
        (field (name "MANUFACTURER") "Cherry")
        (field (name "INTERNAL PART NUMBER") "BTN000004")
        (field (name "KEY FUNCTION") "N")
      )
      (libsource (lib "Altium_Lib_Standard") (part "MX1A-E1NW"))
    )
    (comp (ref "BTN87")
      (value "MX1A-E1NW")
      (footprint "BTN-THT-MX-CHERRY")
      (description "BTN CHERRY MX BLUE SPST-NO 12V 10mA")
      (fields
        (field (name "MANUFACTURER") "Cherry")
        (field (name "INTERNAL PART NUMBER") "BTN000004")
        (field (name "KEY FUNCTION") "M")
      )
      (libsource (lib "Altium_Lib_Standard") (part "MX1A-E1NW"))
    )
    (comp (ref "BTN88")
      (value "MX1A-E1NW")
      (footprint "BTN-THT-MX-CHERRY")
      (description "BTN CHERRY MX BLUE SPST-NO 12V 10mA")
      (fields
        (field (name "MANUFACTURER") "Cherry")
        (field (name "INTERNAL PART NUMBER") "BTN000004")
        (field (name "KEY FUNCTION") ",")
      )
      (libsource (lib "Altium_Lib_Standard") (part "MX1A-E1NW"))
    )
    (comp (ref "BTN89")
      (value "MX1A-E1NW")
      (footprint "BTN-THT-MX-CHERRY")
      (description "BTN CHERRY MX BLUE SPST-NO 12V 10mA")
      (fields
        (field (name "MANUFACTURER") "Cherry")
        (field (name "INTERNAL PART NUMBER") "BTN000004")
        (field (name "KEY FUNCTION") ".")
      )
      (libsource (lib "Altium_Lib_Standard") (part "MX1A-E1NW"))
    )
    (comp (ref "BTN90")
      (value "MX1A-E1NW")
      (footprint "BTN-THT-MX-CHERRY")
      (description "BTN CHERRY MX BLUE SPST-NO 12V 10mA")
      (fields
        (field (name "MANUFACTURER") "Cherry")
        (field (name "INTERNAL PART NUMBER") "BTN000004")
        (field (name "KEY FUNCTION") "-")
      )
      (libsource (lib "Altium_Lib_Standard") (part "MX1A-E1NW"))
    )
    (comp (ref "BTN91")
      (value "MX1A-E1NW")
      (footprint "BTN-THT-MX-CHERRY")
      (description "BTN CHERRY MX BLUE SPST-NO 12V 10mA")
      (fields
        (field (name "MANUFACTURER") "Cherry")
        (field (name "INTERNAL PART NUMBER") "BTN000004")
        (field (name "KEY FUNCTION") "RSHFT")
      )
      (libsource (lib "Altium_Lib_Standard") (part "MX1A-E1NW"))
    )
    (comp (ref "BTN92")
      (value "MX1A-E1NW")
      (footprint "BTN-THT-MX-CHERRY")
      (description "BTN CHERRY MX BLUE SPST-NO 12V 10mA")
      (fields
        (field (name "MANUFACTURER") "Cherry")
        (field (name "INTERNAL PART NUMBER") "BTN000004")
        (field (name "KEY FUNCTION") "M7")
      )
      (libsource (lib "Altium_Lib_Standard") (part "MX1A-E1NW"))
    )
    (comp (ref "BTN93")
      (value "MX1A-E1NW")
      (footprint "BTN-THT-MX-CHERRY")
      (description "BTN CHERRY MX BLUE SPST-NO 12V 10mA")
      (fields
        (field (name "MANUFACTURER") "Cherry")
        (field (name "INTERNAL PART NUMBER") "BTN000004")
        (field (name "KEY FUNCTION") "LCTRL")
      )
      (libsource (lib "Altium_Lib_Standard") (part "MX1A-E1NW"))
    )
    (comp (ref "BTN94")
      (value "MX1A-E1NW")
      (footprint "BTN-THT-MX-CHERRY")
      (description "BTN CHERRY MX BLUE SPST-NO 12V 10mA")
      (fields
        (field (name "MANUFACTURER") "Cherry")
        (field (name "INTERNAL PART NUMBER") "BTN000004")
        (field (name "KEY FUNCTION") "LWIN")
      )
      (libsource (lib "Altium_Lib_Standard") (part "MX1A-E1NW"))
    )
    (comp (ref "BTN95")
      (value "MX1A-E1NW")
      (footprint "BTN-THT-MX-CHERRY")
      (description "BTN CHERRY MX BLUE SPST-NO 12V 10mA")
      (fields
        (field (name "MANUFACTURER") "Cherry")
        (field (name "INTERNAL PART NUMBER") "BTN000004")
        (field (name "KEY FUNCTION") "ALT")
      )
      (libsource (lib "Altium_Lib_Standard") (part "MX1A-E1NW"))
    )
    (comp (ref "BTN96")
      (value "MX1A-E1NW")
      (footprint "BTN-THT-MX-CHERRY")
      (description "BTN CHERRY MX BLUE SPST-NO 12V 10mA")
      (fields
        (field (name "MANUFACTURER") "Cherry")
        (field (name "INTERNAL PART NUMBER") "BTN000004")
        (field (name "KEY FUNCTION") "SPACE")
      )
      (libsource (lib "Altium_Lib_Standard") (part "MX1A-E1NW"))
    )
    (comp (ref "BTN97")
      (value "MX1A-E1NW")
      (footprint "BTN-THT-MX-CHERRY")
      (description "BTN CHERRY MX BLUE SPST-NO 12V 10mA")
      (fields
        (field (name "MANUFACTURER") "Cherry")
        (field (name "INTERNAL PART NUMBER") "BTN000004")
        (field (name "KEY FUNCTION") "ALTGR")
      )
      (libsource (lib "Altium_Lib_Standard") (part "MX1A-E1NW"))
    )
    (comp (ref "BTN98")
      (value "MX1A-E1NW")
      (footprint "BTN-THT-MX-CHERRY")
      (description "BTN CHERRY MX BLUE SPST-NO 12V 10mA")
      (fields
        (field (name "MANUFACTURER") "Cherry")
        (field (name "INTERNAL PART NUMBER") "BTN000004")
        (field (name "KEY FUNCTION") "RWIN")
      )
      (libsource (lib "Altium_Lib_Standard") (part "MX1A-E1NW"))
    )
    (comp (ref "BTN99")
      (value "MX1A-E1NW")
      (footprint "BTN-THT-MX-CHERRY")
      (description "BTN CHERRY MX BLUE SPST-NO 12V 10mA")
      (fields
        (field (name "MANUFACTURER") "Cherry")
        (field (name "INTERNAL PART NUMBER") "BTN000004")
        (field (name "KEY FUNCTION") "FN")
      )
      (libsource (lib "Altium_Lib_Standard") (part "MX1A-E1NW"))
    )
    (comp (ref "BTN100")
      (value "MX1A-E1NW")
      (footprint "BTN-THT-MX-CHERRY")
      (description "BTN CHERRY MX BLUE SPST-NO 12V 10mA")
      (fields
        (field (name "MANUFACTURER") "Cherry")
        (field (name "INTERNAL PART NUMBER") "BTN000004")
        (field (name "KEY FUNCTION") "RCTRL")
      )
      (libsource (lib "Altium_Lib_Standard") (part "MX1A-E1NW"))
    )
    (comp (ref "D1")
      (value "1N4148W-TP")
      (footprint "D-SMD-SOD-123-MICRO-COMMERCIAL-COMPONENTS")
      (description "DIODE GEN-PURP 100V 150mA 1V25@150mA SMD SOD-23")
      (fields (field (name "MANUFACTURER") "MCC") (field (name "INTERNAL PART NUMBER") "D000002"))
      (libsource (lib "Altium_Lib_Standard") (part "1N4148W-TP"))
    )
    (comp (ref "D2")
      (value "1N4148W-TP")
      (footprint "D-SMD-SOD-123-MICRO-COMMERCIAL-COMPONENTS")
      (description "DIODE GEN-PURP 100V 150mA 1V25@150mA SMD SOD-23")
      (fields (field (name "MANUFACTURER") "MCC") (field (name "INTERNAL PART NUMBER") "D000002"))
      (libsource (lib "Altium_Lib_Standard") (part "1N4148W-TP"))
    )
    (comp (ref "D3")
      (value "1N4148W-TP")
      (footprint "D-SMD-SOD-123-MICRO-COMMERCIAL-COMPONENTS")
      (description "DIODE GEN-PURP 100V 150mA 1V25@150mA SMD SOD-23")
      (fields (field (name "MANUFACTURER") "MCC") (field (name "INTERNAL PART NUMBER") "D000002"))
      (libsource (lib "Altium_Lib_Standard") (part "1N4148W-TP"))
    )
    (comp (ref "D4")
      (value "1N4148W-TP")
      (footprint "D-SMD-SOD-123-MICRO-COMMERCIAL-COMPONENTS")
      (description "DIODE GEN-PURP 100V 150mA 1V25@150mA SMD SOD-23")
      (fields (field (name "MANUFACTURER") "MCC") (field (name "INTERNAL PART NUMBER") "D000002"))
      (libsource (lib "Altium_Lib_Standard") (part "1N4148W-TP"))
    )
    (comp (ref "D5")
      (value "1N4148W-TP")
      (footprint "D-SMD-SOD-123-MICRO-COMMERCIAL-COMPONENTS")
      (description "DIODE GEN-PURP 100V 150mA 1V25@150mA SMD SOD-23")
      (fields (field (name "MANUFACTURER") "MCC") (field (name "INTERNAL PART NUMBER") "D000002"))
      (libsource (lib "Altium_Lib_Standard") (part "1N4148W-TP"))
    )
    (comp (ref "D6")
      (value "1N4148W-TP")
      (footprint "D-SMD-SOD-123-MICRO-COMMERCIAL-COMPONENTS")
      (description "DIODE GEN-PURP 100V 150mA 1V25@150mA SMD SOD-23")
      (fields (field (name "MANUFACTURER") "MCC") (field (name "INTERNAL PART NUMBER") "D000002"))
      (libsource (lib "Altium_Lib_Standard") (part "1N4148W-TP"))
    )
    (comp (ref "D7")
      (value "1N4148W-TP")
      (footprint "D-SMD-SOD-123-MICRO-COMMERCIAL-COMPONENTS")
      (description "DIODE GEN-PURP 100V 150mA 1V25@150mA SMD SOD-23")
      (fields (field (name "MANUFACTURER") "MCC") (field (name "INTERNAL PART NUMBER") "D000002"))
      (libsource (lib "Altium_Lib_Standard") (part "1N4148W-TP"))
    )
    (comp (ref "D8")
      (value "1N4148W-TP")
      (footprint "D-SMD-SOD-123-MICRO-COMMERCIAL-COMPONENTS")
      (description "DIODE GEN-PURP 100V 150mA 1V25@150mA SMD SOD-23")
      (fields (field (name "MANUFACTURER") "MCC") (field (name "INTERNAL PART NUMBER") "D000002"))
      (libsource (lib "Altium_Lib_Standard") (part "1N4148W-TP"))
    )
    (comp (ref "D9")
      (value "1N4148W-TP")
      (footprint "D-SMD-SOD-123-MICRO-COMMERCIAL-COMPONENTS")
      (description "DIODE GEN-PURP 100V 150mA 1V25@150mA SMD SOD-23")
      (fields (field (name "MANUFACTURER") "MCC") (field (name "INTERNAL PART NUMBER") "D000002"))
      (libsource (lib "Altium_Lib_Standard") (part "1N4148W-TP"))
    )
    (comp (ref "D10")
      (value "1N4148W-TP")
      (footprint "D-SMD-SOD-123-MICRO-COMMERCIAL-COMPONENTS")
      (description "DIODE GEN-PURP 100V 150mA 1V25@150mA SMD SOD-23")
      (fields (field (name "MANUFACTURER") "MCC") (field (name "INTERNAL PART NUMBER") "D000002"))
      (libsource (lib "Altium_Lib_Standard") (part "1N4148W-TP"))
    )
    (comp (ref "D11")
      (value "1N4148W-TP")
      (footprint "D-SMD-SOD-123-MICRO-COMMERCIAL-COMPONENTS")
      (description "DIODE GEN-PURP 100V 150mA 1V25@150mA SMD SOD-23")
      (fields (field (name "MANUFACTURER") "MCC") (field (name "INTERNAL PART NUMBER") "D000002"))
      (libsource (lib "Altium_Lib_Standard") (part "1N4148W-TP"))
    )
    (comp (ref "D12")
      (value "1N4148W-TP")
      (footprint "D-SMD-SOD-123-MICRO-COMMERCIAL-COMPONENTS")
      (description "DIODE GEN-PURP 100V 150mA 1V25@150mA SMD SOD-23")
      (fields (field (name "MANUFACTURER") "MCC") (field (name "INTERNAL PART NUMBER") "D000002"))
      (libsource (lib "Altium_Lib_Standard") (part "1N4148W-TP"))
    )
    (comp (ref "D13")
      (value "1N4148W-TP")
      (footprint "D-SMD-SOD-123-MICRO-COMMERCIAL-COMPONENTS")
      (description "DIODE GEN-PURP 100V 150mA 1V25@150mA SMD SOD-23")
      (fields (field (name "MANUFACTURER") "MCC") (field (name "INTERNAL PART NUMBER") "D000002"))
      (libsource (lib "Altium_Lib_Standard") (part "1N4148W-TP"))
    )
    (comp (ref "D14")
      (value "1N4148W-TP")
      (footprint "D-SMD-SOD-123-MICRO-COMMERCIAL-COMPONENTS")
      (description "DIODE GEN-PURP 100V 150mA 1V25@150mA SMD SOD-23")
      (fields (field (name "MANUFACTURER") "MCC") (field (name "INTERNAL PART NUMBER") "D000002"))
      (libsource (lib "Altium_Lib_Standard") (part "1N4148W-TP"))
    )
    (comp (ref "D15")
      (value "1N4148W-TP")
      (footprint "D-SMD-SOD-123-MICRO-COMMERCIAL-COMPONENTS")
      (description "DIODE GEN-PURP 100V 150mA 1V25@150mA SMD SOD-23")
      (fields (field (name "MANUFACTURER") "MCC") (field (name "INTERNAL PART NUMBER") "D000002"))
      (libsource (lib "Altium_Lib_Standard") (part "1N4148W-TP"))
    )
    (comp (ref "D16")
      (value "1N4148W-TP")
      (footprint "D-SMD-SOD-123-MICRO-COMMERCIAL-COMPONENTS")
      (description "DIODE GEN-PURP 100V 150mA 1V25@150mA SMD SOD-23")
      (fields (field (name "MANUFACTURER") "MCC") (field (name "INTERNAL PART NUMBER") "D000002"))
      (libsource (lib "Altium_Lib_Standard") (part "1N4148W-TP"))
    )
    (comp (ref "D17")
      (value "1N4148W-TP")
      (footprint "D-SMD-SOD-123-MICRO-COMMERCIAL-COMPONENTS")
      (description "DIODE GEN-PURP 100V 150mA 1V25@150mA SMD SOD-23")
      (fields (field (name "MANUFACTURER") "MCC") (field (name "INTERNAL PART NUMBER") "D000002"))
      (libsource (lib "Altium_Lib_Standard") (part "1N4148W-TP"))
    )
    (comp (ref "D18")
      (value "1N4148W-TP")
      (footprint "D-SMD-SOD-123-MICRO-COMMERCIAL-COMPONENTS")
      (description "DIODE GEN-PURP 100V 150mA 1V25@150mA SMD SOD-23")
      (fields (field (name "MANUFACTURER") "MCC") (field (name "INTERNAL PART NUMBER") "D000002"))
      (libsource (lib "Altium_Lib_Standard") (part "1N4148W-TP"))
    )
    (comp (ref "D19")
      (value "1N4148W-TP")
      (footprint "D-SMD-SOD-123-MICRO-COMMERCIAL-COMPONENTS")
      (description "DIODE GEN-PURP 100V 150mA 1V25@150mA SMD SOD-23")
      (fields (field (name "MANUFACTURER") "MCC") (field (name "INTERNAL PART NUMBER") "D000002"))
      (libsource (lib "Altium_Lib_Standard") (part "1N4148W-TP"))
    )
    (comp (ref "D20")
      (value "1N4148W-TP")
      (footprint "D-SMD-SOD-123-MICRO-COMMERCIAL-COMPONENTS")
      (description "DIODE GEN-PURP 100V 150mA 1V25@150mA SMD SOD-23")
      (fields (field (name "MANUFACTURER") "MCC") (field (name "INTERNAL PART NUMBER") "D000002"))
      (libsource (lib "Altium_Lib_Standard") (part "1N4148W-TP"))
    )
    (comp (ref "D21")
      (value "1N4148W-TP")
      (footprint "D-SMD-SOD-123-MICRO-COMMERCIAL-COMPONENTS")
      (description "DIODE GEN-PURP 100V 150mA 1V25@150mA SMD SOD-23")
      (fields (field (name "MANUFACTURER") "MCC") (field (name "INTERNAL PART NUMBER") "D000002"))
      (libsource (lib "Altium_Lib_Standard") (part "1N4148W-TP"))
    )
    (comp (ref "D22")
      (value "1N4148W-TP")
      (footprint "D-SMD-SOD-123-MICRO-COMMERCIAL-COMPONENTS")
      (description "DIODE GEN-PURP 100V 150mA 1V25@150mA SMD SOD-23")
      (fields (field (name "MANUFACTURER") "MCC") (field (name "INTERNAL PART NUMBER") "D000002"))
      (libsource (lib "Altium_Lib_Standard") (part "1N4148W-TP"))
    )
    (comp (ref "D23")
      (value "1N4148W-TP")
      (footprint "D-SMD-SOD-123-MICRO-COMMERCIAL-COMPONENTS")
      (description "DIODE GEN-PURP 100V 150mA 1V25@150mA SMD SOD-23")
      (fields (field (name "MANUFACTURER") "MCC") (field (name "INTERNAL PART NUMBER") "D000002"))
      (libsource (lib "Altium_Lib_Standard") (part "1N4148W-TP"))
    )
    (comp (ref "D24")
      (value "1N4148W-TP")
      (footprint "D-SMD-SOD-123-MICRO-COMMERCIAL-COMPONENTS")
      (description "DIODE GEN-PURP 100V 150mA 1V25@150mA SMD SOD-23")
      (fields (field (name "MANUFACTURER") "MCC") (field (name "INTERNAL PART NUMBER") "D000002"))
      (libsource (lib "Altium_Lib_Standard") (part "1N4148W-TP"))
    )
    (comp (ref "D25")
      (value "1N4148W-TP")
      (footprint "D-SMD-SOD-123-MICRO-COMMERCIAL-COMPONENTS")
      (description "DIODE GEN-PURP 100V 150mA 1V25@150mA SMD SOD-23")
      (fields (field (name "MANUFACTURER") "MCC") (field (name "INTERNAL PART NUMBER") "D000002"))
      (libsource (lib "Altium_Lib_Standard") (part "1N4148W-TP"))
    )
    (comp (ref "D26")
      (value "1N4148W-TP")
      (footprint "D-SMD-SOD-123-MICRO-COMMERCIAL-COMPONENTS")
      (description "DIODE GEN-PURP 100V 150mA 1V25@150mA SMD SOD-23")
      (fields (field (name "MANUFACTURER") "MCC") (field (name "INTERNAL PART NUMBER") "D000002"))
      (libsource (lib "Altium_Lib_Standard") (part "1N4148W-TP"))
    )
    (comp (ref "D27")
      (value "1N4148W-TP")
      (footprint "D-SMD-SOD-123-MICRO-COMMERCIAL-COMPONENTS")
      (description "DIODE GEN-PURP 100V 150mA 1V25@150mA SMD SOD-23")
      (fields (field (name "MANUFACTURER") "MCC") (field (name "INTERNAL PART NUMBER") "D000002"))
      (libsource (lib "Altium_Lib_Standard") (part "1N4148W-TP"))
    )
    (comp (ref "D28")
      (value "1N4148W-TP")
      (footprint "D-SMD-SOD-123-MICRO-COMMERCIAL-COMPONENTS")
      (description "DIODE GEN-PURP 100V 150mA 1V25@150mA SMD SOD-23")
      (fields (field (name "MANUFACTURER") "MCC") (field (name "INTERNAL PART NUMBER") "D000002"))
      (libsource (lib "Altium_Lib_Standard") (part "1N4148W-TP"))
    )
    (comp (ref "D29")
      (value "1N4148W-TP")
      (footprint "D-SMD-SOD-123-MICRO-COMMERCIAL-COMPONENTS")
      (description "DIODE GEN-PURP 100V 150mA 1V25@150mA SMD SOD-23")
      (fields (field (name "MANUFACTURER") "MCC") (field (name "INTERNAL PART NUMBER") "D000002"))
      (libsource (lib "Altium_Lib_Standard") (part "1N4148W-TP"))
    )
    (comp (ref "D30")
      (value "1N4148W-TP")
      (footprint "D-SMD-SOD-123-MICRO-COMMERCIAL-COMPONENTS")
      (description "DIODE GEN-PURP 100V 150mA 1V25@150mA SMD SOD-23")
      (fields (field (name "MANUFACTURER") "MCC") (field (name "INTERNAL PART NUMBER") "D000002"))
      (libsource (lib "Altium_Lib_Standard") (part "1N4148W-TP"))
    )
    (comp (ref "D31")
      (value "1N4148W-TP")
      (footprint "D-SMD-SOD-123-MICRO-COMMERCIAL-COMPONENTS")
      (description "DIODE GEN-PURP 100V 150mA 1V25@150mA SMD SOD-23")
      (fields (field (name "MANUFACTURER") "MCC") (field (name "INTERNAL PART NUMBER") "D000002"))
      (libsource (lib "Altium_Lib_Standard") (part "1N4148W-TP"))
    )
    (comp (ref "D32")
      (value "1N4148W-TP")
      (footprint "D-SMD-SOD-123-MICRO-COMMERCIAL-COMPONENTS")
      (description "DIODE GEN-PURP 100V 150mA 1V25@150mA SMD SOD-23")
      (fields (field (name "MANUFACTURER") "MCC") (field (name "INTERNAL PART NUMBER") "D000002"))
      (libsource (lib "Altium_Lib_Standard") (part "1N4148W-TP"))
    )
    (comp (ref "D33")
      (value "1N4148W-TP")
      (footprint "D-SMD-SOD-123-MICRO-COMMERCIAL-COMPONENTS")
      (description "DIODE GEN-PURP 100V 150mA 1V25@150mA SMD SOD-23")
      (fields (field (name "MANUFACTURER") "MCC") (field (name "INTERNAL PART NUMBER") "D000002"))
      (libsource (lib "Altium_Lib_Standard") (part "1N4148W-TP"))
    )
    (comp (ref "D34")
      (value "1N4148W-TP")
      (footprint "D-SMD-SOD-123-MICRO-COMMERCIAL-COMPONENTS")
      (description "DIODE GEN-PURP 100V 150mA 1V25@150mA SMD SOD-23")
      (fields (field (name "MANUFACTURER") "MCC") (field (name "INTERNAL PART NUMBER") "D000002"))
      (libsource (lib "Altium_Lib_Standard") (part "1N4148W-TP"))
    )
    (comp (ref "D35")
      (value "1N4148W-TP")
      (footprint "D-SMD-SOD-123-MICRO-COMMERCIAL-COMPONENTS")
      (description "DIODE GEN-PURP 100V 150mA 1V25@150mA SMD SOD-23")
      (fields (field (name "MANUFACTURER") "MCC") (field (name "INTERNAL PART NUMBER") "D000002"))
      (libsource (lib "Altium_Lib_Standard") (part "1N4148W-TP"))
    )
    (comp (ref "D36")
      (value "1N4148W-TP")
      (footprint "D-SMD-SOD-123-MICRO-COMMERCIAL-COMPONENTS")
      (description "DIODE GEN-PURP 100V 150mA 1V25@150mA SMD SOD-23")
      (fields (field (name "MANUFACTURER") "MCC") (field (name "INTERNAL PART NUMBER") "D000002"))
      (libsource (lib "Altium_Lib_Standard") (part "1N4148W-TP"))
    )
    (comp (ref "D37")
      (value "1N4148W-TP")
      (footprint "D-SMD-SOD-123-MICRO-COMMERCIAL-COMPONENTS")
      (description "DIODE GEN-PURP 100V 150mA 1V25@150mA SMD SOD-23")
      (fields (field (name "MANUFACTURER") "MCC") (field (name "INTERNAL PART NUMBER") "D000002"))
      (libsource (lib "Altium_Lib_Standard") (part "1N4148W-TP"))
    )
    (comp (ref "D38")
      (value "1N4148W-TP")
      (footprint "D-SMD-SOD-123-MICRO-COMMERCIAL-COMPONENTS")
      (description "DIODE GEN-PURP 100V 150mA 1V25@150mA SMD SOD-23")
      (fields (field (name "MANUFACTURER") "MCC") (field (name "INTERNAL PART NUMBER") "D000002"))
      (libsource (lib "Altium_Lib_Standard") (part "1N4148W-TP"))
    )
    (comp (ref "D39")
      (value "1N4148W-TP")
      (footprint "D-SMD-SOD-123-MICRO-COMMERCIAL-COMPONENTS")
      (description "DIODE GEN-PURP 100V 150mA 1V25@150mA SMD SOD-23")
      (fields (field (name "MANUFACTURER") "MCC") (field (name "INTERNAL PART NUMBER") "D000002"))
      (libsource (lib "Altium_Lib_Standard") (part "1N4148W-TP"))
    )
    (comp (ref "D40")
      (value "1N4148W-TP")
      (footprint "D-SMD-SOD-123-MICRO-COMMERCIAL-COMPONENTS")
      (description "DIODE GEN-PURP 100V 150mA 1V25@150mA SMD SOD-23")
      (fields (field (name "MANUFACTURER") "MCC") (field (name "INTERNAL PART NUMBER") "D000002"))
      (libsource (lib "Altium_Lib_Standard") (part "1N4148W-TP"))
    )
    (comp (ref "D41")
      (value "1N4148W-TP")
      (footprint "D-SMD-SOD-123-MICRO-COMMERCIAL-COMPONENTS")
      (description "DIODE GEN-PURP 100V 150mA 1V25@150mA SMD SOD-23")
      (fields (field (name "MANUFACTURER") "MCC") (field (name "INTERNAL PART NUMBER") "D000002"))
      (libsource (lib "Altium_Lib_Standard") (part "1N4148W-TP"))
    )
    (comp (ref "D42")
      (value "1N4148W-TP")
      (footprint "D-SMD-SOD-123-MICRO-COMMERCIAL-COMPONENTS")
      (description "DIODE GEN-PURP 100V 150mA 1V25@150mA SMD SOD-23")
      (fields (field (name "MANUFACTURER") "MCC") (field (name "INTERNAL PART NUMBER") "D000002"))
      (libsource (lib "Altium_Lib_Standard") (part "1N4148W-TP"))
    )
    (comp (ref "D43")
      (value "1N4148W-TP")
      (footprint "D-SMD-SOD-123-MICRO-COMMERCIAL-COMPONENTS")
      (description "DIODE GEN-PURP 100V 150mA 1V25@150mA SMD SOD-23")
      (fields (field (name "MANUFACTURER") "MCC") (field (name "INTERNAL PART NUMBER") "D000002"))
      (libsource (lib "Altium_Lib_Standard") (part "1N4148W-TP"))
    )
    (comp (ref "D44")
      (value "1N4148W-TP")
      (footprint "D-SMD-SOD-123-MICRO-COMMERCIAL-COMPONENTS")
      (description "DIODE GEN-PURP 100V 150mA 1V25@150mA SMD SOD-23")
      (fields (field (name "MANUFACTURER") "MCC") (field (name "INTERNAL PART NUMBER") "D000002"))
      (libsource (lib "Altium_Lib_Standard") (part "1N4148W-TP"))
    )
    (comp (ref "D45")
      (value "1N4148W-TP")
      (footprint "D-SMD-SOD-123-MICRO-COMMERCIAL-COMPONENTS")
      (description "DIODE GEN-PURP 100V 150mA 1V25@150mA SMD SOD-23")
      (fields (field (name "MANUFACTURER") "MCC") (field (name "INTERNAL PART NUMBER") "D000002"))
      (libsource (lib "Altium_Lib_Standard") (part "1N4148W-TP"))
    )
    (comp (ref "D46")
      (value "1N4148W-TP")
      (footprint "D-SMD-SOD-123-MICRO-COMMERCIAL-COMPONENTS")
      (description "DIODE GEN-PURP 100V 150mA 1V25@150mA SMD SOD-23")
      (fields (field (name "MANUFACTURER") "MCC") (field (name "INTERNAL PART NUMBER") "D000002"))
      (libsource (lib "Altium_Lib_Standard") (part "1N4148W-TP"))
    )
    (comp (ref "D47")
      (value "1N4148W-TP")
      (footprint "D-SMD-SOD-123-MICRO-COMMERCIAL-COMPONENTS")
      (description "DIODE GEN-PURP 100V 150mA 1V25@150mA SMD SOD-23")
      (fields (field (name "MANUFACTURER") "MCC") (field (name "INTERNAL PART NUMBER") "D000002"))
      (libsource (lib "Altium_Lib_Standard") (part "1N4148W-TP"))
    )
    (comp (ref "D48")
      (value "1N4148W-TP")
      (footprint "D-SMD-SOD-123-MICRO-COMMERCIAL-COMPONENTS")
      (description "DIODE GEN-PURP 100V 150mA 1V25@150mA SMD SOD-23")
      (fields (field (name "MANUFACTURER") "MCC") (field (name "INTERNAL PART NUMBER") "D000002"))
      (libsource (lib "Altium_Lib_Standard") (part "1N4148W-TP"))
    )
    (comp (ref "D49")
      (value "1N4148W-TP")
      (footprint "D-SMD-SOD-123-MICRO-COMMERCIAL-COMPONENTS")
      (description "DIODE GEN-PURP 100V 150mA 1V25@150mA SMD SOD-23")
      (fields (field (name "MANUFACTURER") "MCC") (field (name "INTERNAL PART NUMBER") "D000002"))
      (libsource (lib "Altium_Lib_Standard") (part "1N4148W-TP"))
    )
    (comp (ref "D50")
      (value "1N4148W-TP")
      (footprint "D-SMD-SOD-123-MICRO-COMMERCIAL-COMPONENTS")
      (description "DIODE GEN-PURP 100V 150mA 1V25@150mA SMD SOD-23")
      (fields (field (name "MANUFACTURER") "MCC") (field (name "INTERNAL PART NUMBER") "D000002"))
      (libsource (lib "Altium_Lib_Standard") (part "1N4148W-TP"))
    )
    (comp (ref "D51")
      (value "1N4148W-TP")
      (footprint "D-SMD-SOD-123-MICRO-COMMERCIAL-COMPONENTS")
      (description "DIODE GEN-PURP 100V 150mA 1V25@150mA SMD SOD-23")
      (fields (field (name "MANUFACTURER") "MCC") (field (name "INTERNAL PART NUMBER") "D000002"))
      (libsource (lib "Altium_Lib_Standard") (part "1N4148W-TP"))
    )
    (comp (ref "D52")
      (value "1N4148W-TP")
      (footprint "D-SMD-SOD-123-MICRO-COMMERCIAL-COMPONENTS")
      (description "DIODE GEN-PURP 100V 150mA 1V25@150mA SMD SOD-23")
      (fields (field (name "MANUFACTURER") "MCC") (field (name "INTERNAL PART NUMBER") "D000002"))
      (libsource (lib "Altium_Lib_Standard") (part "1N4148W-TP"))
    )
    (comp (ref "D53")
      (value "1N4148W-TP")
      (footprint "D-SMD-SOD-123-MICRO-COMMERCIAL-COMPONENTS")
      (description "DIODE GEN-PURP 100V 150mA 1V25@150mA SMD SOD-23")
      (fields (field (name "MANUFACTURER") "MCC") (field (name "INTERNAL PART NUMBER") "D000002"))
      (libsource (lib "Altium_Lib_Standard") (part "1N4148W-TP"))
    )
    (comp (ref "D54")
      (value "1N4148W-TP")
      (footprint "D-SMD-SOD-123-MICRO-COMMERCIAL-COMPONENTS")
      (description "DIODE GEN-PURP 100V 150mA 1V25@150mA SMD SOD-23")
      (fields (field (name "MANUFACTURER") "MCC") (field (name "INTERNAL PART NUMBER") "D000002"))
      (libsource (lib "Altium_Lib_Standard") (part "1N4148W-TP"))
    )
    (comp (ref "D55")
      (value "1N4148W-TP")
      (footprint "D-SMD-SOD-123-MICRO-COMMERCIAL-COMPONENTS")
      (description "DIODE GEN-PURP 100V 150mA 1V25@150mA SMD SOD-23")
      (fields (field (name "MANUFACTURER") "MCC") (field (name "INTERNAL PART NUMBER") "D000002"))
      (libsource (lib "Altium_Lib_Standard") (part "1N4148W-TP"))
    )
    (comp (ref "D56")
      (value "1N4148W-TP")
      (footprint "D-SMD-SOD-123-MICRO-COMMERCIAL-COMPONENTS")
      (description "DIODE GEN-PURP 100V 150mA 1V25@150mA SMD SOD-23")
      (fields (field (name "MANUFACTURER") "MCC") (field (name "INTERNAL PART NUMBER") "D000002"))
      (libsource (lib "Altium_Lib_Standard") (part "1N4148W-TP"))
    )
    (comp (ref "D57")
      (value "1N4148W-TP")
      (footprint "D-SMD-SOD-123-MICRO-COMMERCIAL-COMPONENTS")
      (description "DIODE GEN-PURP 100V 150mA 1V25@150mA SMD SOD-23")
      (fields (field (name "MANUFACTURER") "MCC") (field (name "INTERNAL PART NUMBER") "D000002"))
      (libsource (lib "Altium_Lib_Standard") (part "1N4148W-TP"))
    )
    (comp (ref "D58")
      (value "1N4148W-TP")
      (footprint "D-SMD-SOD-123-MICRO-COMMERCIAL-COMPONENTS")
      (description "DIODE GEN-PURP 100V 150mA 1V25@150mA SMD SOD-23")
      (fields (field (name "MANUFACTURER") "MCC") (field (name "INTERNAL PART NUMBER") "D000002"))
      (libsource (lib "Altium_Lib_Standard") (part "1N4148W-TP"))
    )
    (comp (ref "D59")
      (value "1N4148W-TP")
      (footprint "D-SMD-SOD-123-MICRO-COMMERCIAL-COMPONENTS")
      (description "DIODE GEN-PURP 100V 150mA 1V25@150mA SMD SOD-23")
      (fields (field (name "MANUFACTURER") "MCC") (field (name "INTERNAL PART NUMBER") "D000002"))
      (libsource (lib "Altium_Lib_Standard") (part "1N4148W-TP"))
    )
    (comp (ref "D60")
      (value "1N4148W-TP")
      (footprint "D-SMD-SOD-123-MICRO-COMMERCIAL-COMPONENTS")
      (description "DIODE GEN-PURP 100V 150mA 1V25@150mA SMD SOD-23")
      (fields (field (name "MANUFACTURER") "MCC") (field (name "INTERNAL PART NUMBER") "D000002"))
      (libsource (lib "Altium_Lib_Standard") (part "1N4148W-TP"))
    )
    (comp (ref "D61")
      (value "1N4148W-TP")
      (footprint "D-SMD-SOD-123-MICRO-COMMERCIAL-COMPONENTS")
      (description "DIODE GEN-PURP 100V 150mA 1V25@150mA SMD SOD-23")
      (fields (field (name "MANUFACTURER") "MCC") (field (name "INTERNAL PART NUMBER") "D000002"))
      (libsource (lib "Altium_Lib_Standard") (part "1N4148W-TP"))
    )
    (comp (ref "D62")
      (value "1N4148W-TP")
      (footprint "D-SMD-SOD-123-MICRO-COMMERCIAL-COMPONENTS")
      (description "DIODE GEN-PURP 100V 150mA 1V25@150mA SMD SOD-23")
      (fields (field (name "MANUFACTURER") "MCC") (field (name "INTERNAL PART NUMBER") "D000002"))
      (libsource (lib "Altium_Lib_Standard") (part "1N4148W-TP"))
    )
    (comp (ref "D63")
      (value "1N4148W-TP")
      (footprint "D-SMD-SOD-123-MICRO-COMMERCIAL-COMPONENTS")
      (description "DIODE GEN-PURP 100V 150mA 1V25@150mA SMD SOD-23")
      (fields (field (name "MANUFACTURER") "MCC") (field (name "INTERNAL PART NUMBER") "D000002"))
      (libsource (lib "Altium_Lib_Standard") (part "1N4148W-TP"))
    )
    (comp (ref "D64")
      (value "1N4148W-TP")
      (footprint "D-SMD-SOD-123-MICRO-COMMERCIAL-COMPONENTS")
      (description "DIODE GEN-PURP 100V 150mA 1V25@150mA SMD SOD-23")
      (fields (field (name "MANUFACTURER") "MCC") (field (name "INTERNAL PART NUMBER") "D000002"))
      (libsource (lib "Altium_Lib_Standard") (part "1N4148W-TP"))
    )
    (comp (ref "D65")
      (value "1N4148W-TP")
      (footprint "D-SMD-SOD-123-MICRO-COMMERCIAL-COMPONENTS")
      (description "DIODE GEN-PURP 100V 150mA 1V25@150mA SMD SOD-23")
      (fields (field (name "MANUFACTURER") "MCC") (field (name "INTERNAL PART NUMBER") "D000002"))
      (libsource (lib "Altium_Lib_Standard") (part "1N4148W-TP"))
    )
    (comp (ref "D66")
      (value "1N4148W-TP")
      (footprint "D-SMD-SOD-123-MICRO-COMMERCIAL-COMPONENTS")
      (description "DIODE GEN-PURP 100V 150mA 1V25@150mA SMD SOD-23")
      (fields (field (name "MANUFACTURER") "MCC") (field (name "INTERNAL PART NUMBER") "D000002"))
      (libsource (lib "Altium_Lib_Standard") (part "1N4148W-TP"))
    )
    (comp (ref "D67")
      (value "1N4148W-TP")
      (footprint "D-SMD-SOD-123-MICRO-COMMERCIAL-COMPONENTS")
      (description "DIODE GEN-PURP 100V 150mA 1V25@150mA SMD SOD-23")
      (fields (field (name "MANUFACTURER") "MCC") (field (name "INTERNAL PART NUMBER") "D000002"))
      (libsource (lib "Altium_Lib_Standard") (part "1N4148W-TP"))
    )
    (comp (ref "D68")
      (value "1N4148W-TP")
      (footprint "D-SMD-SOD-123-MICRO-COMMERCIAL-COMPONENTS")
      (description "DIODE GEN-PURP 100V 150mA 1V25@150mA SMD SOD-23")
      (fields (field (name "MANUFACTURER") "MCC") (field (name "INTERNAL PART NUMBER") "D000002"))
      (libsource (lib "Altium_Lib_Standard") (part "1N4148W-TP"))
    )
    (comp (ref "D69")
      (value "1N4148W-TP")
      (footprint "D-SMD-SOD-123-MICRO-COMMERCIAL-COMPONENTS")
      (description "DIODE GEN-PURP 100V 150mA 1V25@150mA SMD SOD-23")
      (fields (field (name "MANUFACTURER") "MCC") (field (name "INTERNAL PART NUMBER") "D000002"))
      (libsource (lib "Altium_Lib_Standard") (part "1N4148W-TP"))
    )
    (comp (ref "D70")
      (value "1N4148W-TP")
      (footprint "D-SMD-SOD-123-MICRO-COMMERCIAL-COMPONENTS")
      (description "DIODE GEN-PURP 100V 150mA 1V25@150mA SMD SOD-23")
      (fields (field (name "MANUFACTURER") "MCC") (field (name "INTERNAL PART NUMBER") "D000002"))
      (libsource (lib "Altium_Lib_Standard") (part "1N4148W-TP"))
    )
    (comp (ref "D71")
      (value "1N4148W-TP")
      (footprint "D-SMD-SOD-123-MICRO-COMMERCIAL-COMPONENTS")
      (description "DIODE GEN-PURP 100V 150mA 1V25@150mA SMD SOD-23")
      (fields (field (name "MANUFACTURER") "MCC") (field (name "INTERNAL PART NUMBER") "D000002"))
      (libsource (lib "Altium_Lib_Standard") (part "1N4148W-TP"))
    )
    (comp (ref "D72")
      (value "1N4148W-TP")
      (footprint "D-SMD-SOD-123-MICRO-COMMERCIAL-COMPONENTS")
      (description "DIODE GEN-PURP 100V 150mA 1V25@150mA SMD SOD-23")
      (fields (field (name "MANUFACTURER") "MCC") (field (name "INTERNAL PART NUMBER") "D000002"))
      (libsource (lib "Altium_Lib_Standard") (part "1N4148W-TP"))
    )
    (comp (ref "D73")
      (value "1N4148W-TP")
      (footprint "D-SMD-SOD-123-MICRO-COMMERCIAL-COMPONENTS")
      (description "DIODE GEN-PURP 100V 150mA 1V25@150mA SMD SOD-23")
      (fields (field (name "MANUFACTURER") "MCC") (field (name "INTERNAL PART NUMBER") "D000002"))
      (libsource (lib "Altium_Lib_Standard") (part "1N4148W-TP"))
    )
    (comp (ref "D74")
      (value "1N4148W-TP")
      (footprint "D-SMD-SOD-123-MICRO-COMMERCIAL-COMPONENTS")
      (description "DIODE GEN-PURP 100V 150mA 1V25@150mA SMD SOD-23")
      (fields (field (name "MANUFACTURER") "MCC") (field (name "INTERNAL PART NUMBER") "D000002"))
      (libsource (lib "Altium_Lib_Standard") (part "1N4148W-TP"))
    )
    (comp (ref "D75")
      (value "1N4148W-TP")
      (footprint "D-SMD-SOD-123-MICRO-COMMERCIAL-COMPONENTS")
      (description "DIODE GEN-PURP 100V 150mA 1V25@150mA SMD SOD-23")
      (fields (field (name "MANUFACTURER") "MCC") (field (name "INTERNAL PART NUMBER") "D000002"))
      (libsource (lib "Altium_Lib_Standard") (part "1N4148W-TP"))
    )
    (comp (ref "D76")
      (value "1N4148W-TP")
      (footprint "D-SMD-SOD-123-MICRO-COMMERCIAL-COMPONENTS")
      (description "DIODE GEN-PURP 100V 150mA 1V25@150mA SMD SOD-23")
      (fields (field (name "MANUFACTURER") "MCC") (field (name "INTERNAL PART NUMBER") "D000002"))
      (libsource (lib "Altium_Lib_Standard") (part "1N4148W-TP"))
    )
    (comp (ref "D77")
      (value "1N4148W-TP")
      (footprint "D-SMD-SOD-123-MICRO-COMMERCIAL-COMPONENTS")
      (description "DIODE GEN-PURP 100V 150mA 1V25@150mA SMD SOD-23")
      (fields (field (name "MANUFACTURER") "MCC") (field (name "INTERNAL PART NUMBER") "D000002"))
      (libsource (lib "Altium_Lib_Standard") (part "1N4148W-TP"))
    )
    (comp (ref "D78")
      (value "1N4148W-TP")
      (footprint "D-SMD-SOD-123-MICRO-COMMERCIAL-COMPONENTS")
      (description "DIODE GEN-PURP 100V 150mA 1V25@150mA SMD SOD-23")
      (fields (field (name "MANUFACTURER") "MCC") (field (name "INTERNAL PART NUMBER") "D000002"))
      (libsource (lib "Altium_Lib_Standard") (part "1N4148W-TP"))
    )
    (comp (ref "D79")
      (value "1N4148W-TP")
      (footprint "D-SMD-SOD-123-MICRO-COMMERCIAL-COMPONENTS")
      (description "DIODE GEN-PURP 100V 150mA 1V25@150mA SMD SOD-23")
      (fields (field (name "MANUFACTURER") "MCC") (field (name "INTERNAL PART NUMBER") "D000002"))
      (libsource (lib "Altium_Lib_Standard") (part "1N4148W-TP"))
    )
    (comp (ref "D80")
      (value "1N4148W-TP")
      (footprint "D-SMD-SOD-123-MICRO-COMMERCIAL-COMPONENTS")
      (description "DIODE GEN-PURP 100V 150mA 1V25@150mA SMD SOD-23")
      (fields (field (name "MANUFACTURER") "MCC") (field (name "INTERNAL PART NUMBER") "D000002"))
      (libsource (lib "Altium_Lib_Standard") (part "1N4148W-TP"))
    )
    (comp (ref "D81")
      (value "1N4148W-TP")
      (footprint "D-SMD-SOD-123-MICRO-COMMERCIAL-COMPONENTS")
      (description "DIODE GEN-PURP 100V 150mA 1V25@150mA SMD SOD-23")
      (fields (field (name "MANUFACTURER") "MCC") (field (name "INTERNAL PART NUMBER") "D000002"))
      (libsource (lib "Altium_Lib_Standard") (part "1N4148W-TP"))
    )
    (comp (ref "D82")
      (value "1N4148W-TP")
      (footprint "D-SMD-SOD-123-MICRO-COMMERCIAL-COMPONENTS")
      (description "DIODE GEN-PURP 100V 150mA 1V25@150mA SMD SOD-23")
      (fields (field (name "MANUFACTURER") "MCC") (field (name "INTERNAL PART NUMBER") "D000002"))
      (libsource (lib "Altium_Lib_Standard") (part "1N4148W-TP"))
    )
    (comp (ref "D83")
      (value "1N4148W-TP")
      (footprint "D-SMD-SOD-123-MICRO-COMMERCIAL-COMPONENTS")
      (description "DIODE GEN-PURP 100V 150mA 1V25@150mA SMD SOD-23")
      (fields (field (name "MANUFACTURER") "MCC") (field (name "INTERNAL PART NUMBER") "D000002"))
      (libsource (lib "Altium_Lib_Standard") (part "1N4148W-TP"))
    )
    (comp (ref "D84")
      (value "1N4148W-TP")
      (footprint "D-SMD-SOD-123-MICRO-COMMERCIAL-COMPONENTS")
      (description "DIODE GEN-PURP 100V 150mA 1V25@150mA SMD SOD-23")
      (fields (field (name "MANUFACTURER") "MCC") (field (name "INTERNAL PART NUMBER") "D000002"))
      (libsource (lib "Altium_Lib_Standard") (part "1N4148W-TP"))
    )
    (comp (ref "D85")
      (value "1N4148W-TP")
      (footprint "D-SMD-SOD-123-MICRO-COMMERCIAL-COMPONENTS")
      (description "DIODE GEN-PURP 100V 150mA 1V25@150mA SMD SOD-23")
      (fields (field (name "MANUFACTURER") "MCC") (field (name "INTERNAL PART NUMBER") "D000002"))
      (libsource (lib "Altium_Lib_Standard") (part "1N4148W-TP"))
    )
    (comp (ref "D86")
      (value "1N4148W-TP")
      (footprint "D-SMD-SOD-123-MICRO-COMMERCIAL-COMPONENTS")
      (description "DIODE GEN-PURP 100V 150mA 1V25@150mA SMD SOD-23")
      (fields (field (name "MANUFACTURER") "MCC") (field (name "INTERNAL PART NUMBER") "D000002"))
      (libsource (lib "Altium_Lib_Standard") (part "1N4148W-TP"))
    )
    (comp (ref "D87")
      (value "1N4148W-TP")
      (footprint "D-SMD-SOD-123-MICRO-COMMERCIAL-COMPONENTS")
      (description "DIODE GEN-PURP 100V 150mA 1V25@150mA SMD SOD-23")
      (fields (field (name "MANUFACTURER") "MCC") (field (name "INTERNAL PART NUMBER") "D000002"))
      (libsource (lib "Altium_Lib_Standard") (part "1N4148W-TP"))
    )
    (comp (ref "D88")
      (value "1N4148W-TP")
      (footprint "D-SMD-SOD-123-MICRO-COMMERCIAL-COMPONENTS")
      (description "DIODE GEN-PURP 100V 150mA 1V25@150mA SMD SOD-23")
      (fields (field (name "MANUFACTURER") "MCC") (field (name "INTERNAL PART NUMBER") "D000002"))
      (libsource (lib "Altium_Lib_Standard") (part "1N4148W-TP"))
    )
    (comp (ref "D89")
      (value "1N4148W-TP")
      (footprint "D-SMD-SOD-123-MICRO-COMMERCIAL-COMPONENTS")
      (description "DIODE GEN-PURP 100V 150mA 1V25@150mA SMD SOD-23")
      (fields (field (name "MANUFACTURER") "MCC") (field (name "INTERNAL PART NUMBER") "D000002"))
      (libsource (lib "Altium_Lib_Standard") (part "1N4148W-TP"))
    )
    (comp (ref "D90")
      (value "1N4148W-TP")
      (footprint "D-SMD-SOD-123-MICRO-COMMERCIAL-COMPONENTS")
      (description "DIODE GEN-PURP 100V 150mA 1V25@150mA SMD SOD-23")
      (fields (field (name "MANUFACTURER") "MCC") (field (name "INTERNAL PART NUMBER") "D000002"))
      (libsource (lib "Altium_Lib_Standard") (part "1N4148W-TP"))
    )
    (comp (ref "D91")
      (value "1N4148W-TP")
      (footprint "D-SMD-SOD-123-MICRO-COMMERCIAL-COMPONENTS")
      (description "DIODE GEN-PURP 100V 150mA 1V25@150mA SMD SOD-23")
      (fields (field (name "MANUFACTURER") "MCC") (field (name "INTERNAL PART NUMBER") "D000002"))
      (libsource (lib "Altium_Lib_Standard") (part "1N4148W-TP"))
    )
    (comp (ref "D92")
      (value "1N4148W-TP")
      (footprint "D-SMD-SOD-123-MICRO-COMMERCIAL-COMPONENTS")
      (description "DIODE GEN-PURP 100V 150mA 1V25@150mA SMD SOD-23")
      (fields (field (name "MANUFACTURER") "MCC") (field (name "INTERNAL PART NUMBER") "D000002"))
      (libsource (lib "Altium_Lib_Standard") (part "1N4148W-TP"))
    )
    (comp (ref "D93")
      (value "1N4148W-TP")
      (footprint "D-SMD-SOD-123-MICRO-COMMERCIAL-COMPONENTS")
      (description "DIODE GEN-PURP 100V 150mA 1V25@150mA SMD SOD-23")
      (fields (field (name "MANUFACTURER") "MCC") (field (name "INTERNAL PART NUMBER") "D000002"))
      (libsource (lib "Altium_Lib_Standard") (part "1N4148W-TP"))
    )
    (comp (ref "D94")
      (value "1N4148W-TP")
      (footprint "D-SMD-SOD-123-MICRO-COMMERCIAL-COMPONENTS")
      (description "DIODE GEN-PURP 100V 150mA 1V25@150mA SMD SOD-23")
      (fields (field (name "MANUFACTURER") "MCC") (field (name "INTERNAL PART NUMBER") "D000002"))
      (libsource (lib "Altium_Lib_Standard") (part "1N4148W-TP"))
    )
    (comp (ref "D95")
      (value "1N4148W-TP")
      (footprint "D-SMD-SOD-123-MICRO-COMMERCIAL-COMPONENTS")
      (description "DIODE GEN-PURP 100V 150mA 1V25@150mA SMD SOD-23")
      (fields (field (name "MANUFACTURER") "MCC") (field (name "INTERNAL PART NUMBER") "D000002"))
      (libsource (lib "Altium_Lib_Standard") (part "1N4148W-TP"))
    )
    (comp (ref "D96")
      (value "1N4148W-TP")
      (footprint "D-SMD-SOD-123-MICRO-COMMERCIAL-COMPONENTS")
      (description "DIODE GEN-PURP 100V 150mA 1V25@150mA SMD SOD-23")
      (fields (field (name "MANUFACTURER") "MCC") (field (name "INTERNAL PART NUMBER") "D000002"))
      (libsource (lib "Altium_Lib_Standard") (part "1N4148W-TP"))
    )
    (comp (ref "D97")
      (value "1N4148W-TP")
      (footprint "D-SMD-SOD-123-MICRO-COMMERCIAL-COMPONENTS")
      (description "DIODE GEN-PURP 100V 150mA 1V25@150mA SMD SOD-23")
      (fields (field (name "MANUFACTURER") "MCC") (field (name "INTERNAL PART NUMBER") "D000002"))
      (libsource (lib "Altium_Lib_Standard") (part "1N4148W-TP"))
    )
    (comp (ref "D98")
      (value "1N4148W-TP")
      (footprint "D-SMD-SOD-123-MICRO-COMMERCIAL-COMPONENTS")
      (description "DIODE GEN-PURP 100V 150mA 1V25@150mA SMD SOD-23")
      (fields (field (name "MANUFACTURER") "MCC") (field (name "INTERNAL PART NUMBER") "D000002"))
      (libsource (lib "Altium_Lib_Standard") (part "1N4148W-TP"))
    )
    (comp (ref "D99")
      (value "1N4148W-TP")
      (footprint "D-SMD-SOD-123-MICRO-COMMERCIAL-COMPONENTS")
      (description "DIODE GEN-PURP 100V 150mA 1V25@150mA SMD SOD-23")
      (fields (field (name "MANUFACTURER") "MCC") (field (name "INTERNAL PART NUMBER") "D000002"))
      (libsource (lib "Altium_Lib_Standard") (part "1N4148W-TP"))
    )
    (comp (ref "R3")
      (value "10kR 1%")
      (footprint "RES-SMD-0402-0.4MM-IPC-MED")
      (description "RES 10K 1% 1/16W SMD 0402 YAEGO")
      (fields
        (field (name "MANUFACTURER") "Yageo")
        (field (name "MANUFACTURER PART NUMBER") "RC0402FR-0710KL")
        (field (name "TOLERANCE") "1%")
        (field (name "TEMPERATURE COEFFICIENT") "100ppm/°C")
        (field (name "RESISTANCE") "10kR")
        (field (name "POWER RATING") "62.5mW")
        (field (name "CASE CODE (IMPERIAL)") "0402")
        (field (name "INTERNAL PART NUMBER") "R000016")
      )
      (libsource (lib "Altium_Lib_Standard") (part "RC0402FR-0710KL"))
    )
    (comp (ref "R4")
      (value "10kR 1%")
      (footprint "RES-SMD-0402-0.4MM-IPC-MED")
      (description "RES 10K 1% 1/16W SMD 0402 YAEGO")
      (fields
        (field (name "MANUFACTURER") "Yageo")
        (field (name "MANUFACTURER PART NUMBER") "RC0402FR-0710KL")
        (field (name "TOLERANCE") "1%")
        (field (name "TEMPERATURE COEFFICIENT") "100ppm/°C")
        (field (name "RESISTANCE") "10kR")
        (field (name "POWER RATING") "62.5mW")
        (field (name "CASE CODE (IMPERIAL)") "0402")
        (field (name "INTERNAL PART NUMBER") "R000016")
      )
      (libsource (lib "Altium_Lib_Standard") (part "RC0402FR-0710KL"))
    )
    (comp (ref "R5")
      (value "10kR 1%")
      (footprint "RES-SMD-0402-0.4MM-IPC-MED")
      (description "RES 10K 1% 1/16W SMD 0402 YAEGO")
      (fields
        (field (name "MANUFACTURER") "Yageo")
        (field (name "MANUFACTURER PART NUMBER") "RC0402FR-0710KL")
        (field (name "TOLERANCE") "1%")
        (field (name "TEMPERATURE COEFFICIENT") "100ppm/°C")
        (field (name "RESISTANCE") "10kR")
        (field (name "POWER RATING") "62.5mW")
        (field (name "CASE CODE (IMPERIAL)") "0402")
        (field (name "INTERNAL PART NUMBER") "R000016")
      )
      (libsource (lib "Altium_Lib_Standard") (part "RC0402FR-0710KL"))
    )
    (comp (ref "R6")
      (value "10kR 1%")
      (footprint "RES-SMD-0402-0.4MM-IPC-MED")
      (description "RES 10K 1% 1/16W SMD 0402 YAEGO")
      (fields
        (field (name "MANUFACTURER") "Yageo")
        (field (name "MANUFACTURER PART NUMBER") "RC0402FR-0710KL")
        (field (name "TOLERANCE") "1%")
        (field (name "TEMPERATURE COEFFICIENT") "100ppm/°C")
        (field (name "RESISTANCE") "10kR")
        (field (name "POWER RATING") "62.5mW")
        (field (name "CASE CODE (IMPERIAL)") "0402")
        (field (name "INTERNAL PART NUMBER") "R000016")
      )
      (libsource (lib "Altium_Lib_Standard") (part "RC0402FR-0710KL"))
    )
    (comp (ref "R7")
      (value "10kR 1%")
      (footprint "RES-SMD-0402-0.4MM-IPC-MED")
      (description "RES 10K 1% 1/16W SMD 0402 YAEGO")
      (fields
        (field (name "MANUFACTURER") "Yageo")
        (field (name "MANUFACTURER PART NUMBER") "RC0402FR-0710KL")
        (field (name "TOLERANCE") "1%")
        (field (name "TEMPERATURE COEFFICIENT") "100ppm/°C")
        (field (name "RESISTANCE") "10kR")
        (field (name "POWER RATING") "62.5mW")
        (field (name "CASE CODE (IMPERIAL)") "0402")
        (field (name "INTERNAL PART NUMBER") "R000016")
      )
      (libsource (lib "Altium_Lib_Standard") (part "RC0402FR-0710KL"))
    )
    (comp (ref "R8")
      (value "10kR 1%")
      (footprint "RES-SMD-0402-0.4MM-IPC-MED")
      (description "RES 10K 1% 1/16W SMD 0402 YAEGO")
      (fields
        (field (name "MANUFACTURER") "Yageo")
        (field (name "MANUFACTURER PART NUMBER") "RC0402FR-0710KL")
        (field (name "TOLERANCE") "1%")
        (field (name "TEMPERATURE COEFFICIENT") "100ppm/°C")
        (field (name "RESISTANCE") "10kR")
        (field (name "POWER RATING") "62.5mW")
        (field (name "CASE CODE (IMPERIAL)") "0402")
        (field (name "INTERNAL PART NUMBER") "R000016")
      )
      (libsource (lib "Altium_Lib_Standard") (part "RC0402FR-0710KL"))
    )
    (comp (ref "R9")
      (value "10kR 1%")
      (footprint "RES-SMD-0402-0.4MM-IPC-MED")
      (description "RES 10K 1% 1/16W SMD 0402 YAEGO")
      (fields
        (field (name "MANUFACTURER") "Yageo")
        (field (name "MANUFACTURER PART NUMBER") "RC0402FR-0710KL")
        (field (name "TOLERANCE") "1%")
        (field (name "TEMPERATURE COEFFICIENT") "100ppm/°C")
        (field (name "RESISTANCE") "10kR")
        (field (name "POWER RATING") "62.5mW")
        (field (name "CASE CODE (IMPERIAL)") "0402")
        (field (name "INTERNAL PART NUMBER") "R000016")
      )
      (libsource (lib "Altium_Lib_Standard") (part "RC0402FR-0710KL"))
    )
    (comp (ref "R10")
      (value "10kR 1%")
      (footprint "RES-SMD-0402-0.4MM-IPC-MED")
      (description "RES 10K 1% 1/16W SMD 0402 YAEGO")
      (fields
        (field (name "MANUFACTURER") "Yageo")
        (field (name "MANUFACTURER PART NUMBER") "RC0402FR-0710KL")
        (field (name "TOLERANCE") "1%")
        (field (name "TEMPERATURE COEFFICIENT") "100ppm/°C")
        (field (name "RESISTANCE") "10kR")
        (field (name "POWER RATING") "62.5mW")
        (field (name "CASE CODE (IMPERIAL)") "0402")
        (field (name "INTERNAL PART NUMBER") "R000016")
      )
      (libsource (lib "Altium_Lib_Standard") (part "RC0402FR-0710KL"))
    )
    (comp (ref "R11")
      (value "10kR 1%")
      (footprint "RES-SMD-0402-0.4MM-IPC-MED")
      (description "RES 10K 1% 1/16W SMD 0402 YAEGO")
      (fields
        (field (name "MANUFACTURER") "Yageo")
        (field (name "MANUFACTURER PART NUMBER") "RC0402FR-0710KL")
        (field (name "TOLERANCE") "1%")
        (field (name "TEMPERATURE COEFFICIENT") "100ppm/°C")
        (field (name "RESISTANCE") "10kR")
        (field (name "POWER RATING") "62.5mW")
        (field (name "CASE CODE (IMPERIAL)") "0402")
        (field (name "INTERNAL PART NUMBER") "R000016")
      )
      (libsource (lib "Altium_Lib_Standard") (part "RC0402FR-0710KL"))
    )
    (comp (ref "R12")
      (value "10kR 1%")
      (footprint "RES-SMD-0402-0.4MM-IPC-MED")
      (description "RES 10K 1% 1/16W SMD 0402 YAEGO")
      (fields
        (field (name "MANUFACTURER") "Yageo")
        (field (name "MANUFACTURER PART NUMBER") "RC0402FR-0710KL")
        (field (name "TOLERANCE") "1%")
        (field (name "TEMPERATURE COEFFICIENT") "100ppm/°C")
        (field (name "RESISTANCE") "10kR")
        (field (name "POWER RATING") "62.5mW")
        (field (name "CASE CODE (IMPERIAL)") "0402")
        (field (name "INTERNAL PART NUMBER") "R000016")
      )
      (libsource (lib "Altium_Lib_Standard") (part "RC0402FR-0710KL"))
    )
    (comp (ref "R13")
      (value "10kR 1%")
      (footprint "RES-SMD-0402-0.4MM-IPC-MED")
      (description "RES 10K 1% 1/16W SMD 0402 YAEGO")
      (fields
        (field (name "MANUFACTURER") "Yageo")
        (field (name "MANUFACTURER PART NUMBER") "RC0402FR-0710KL")
        (field (name "TOLERANCE") "1%")
        (field (name "TEMPERATURE COEFFICIENT") "100ppm/°C")
        (field (name "RESISTANCE") "10kR")
        (field (name "POWER RATING") "62.5mW")
        (field (name "CASE CODE (IMPERIAL)") "0402")
        (field (name "INTERNAL PART NUMBER") "R000016")
      )
      (libsource (lib "Altium_Lib_Standard") (part "RC0402FR-0710KL"))
    )
    (comp (ref "R14")
      (value "10kR 1%")
      (footprint "RES-SMD-0402-0.4MM-IPC-MED")
      (description "RES 10K 1% 1/16W SMD 0402 YAEGO")
      (fields
        (field (name "MANUFACTURER") "Yageo")
        (field (name "MANUFACTURER PART NUMBER") "RC0402FR-0710KL")
        (field (name "TOLERANCE") "1%")
        (field (name "TEMPERATURE COEFFICIENT") "100ppm/°C")
        (field (name "RESISTANCE") "10kR")
        (field (name "POWER RATING") "62.5mW")
        (field (name "CASE CODE (IMPERIAL)") "0402")
        (field (name "INTERNAL PART NUMBER") "R000016")
      )
      (libsource (lib "Altium_Lib_Standard") (part "RC0402FR-0710KL"))
    )
    (comp (ref "R15")
      (value "10kR 1%")
      (footprint "RES-SMD-0402-0.4MM-IPC-MED")
      (description "RES 10K 1% 1/16W SMD 0402 YAEGO")
      (fields
        (field (name "MANUFACTURER") "Yageo")
        (field (name "MANUFACTURER PART NUMBER") "RC0402FR-0710KL")
        (field (name "TOLERANCE") "1%")
        (field (name "TEMPERATURE COEFFICIENT") "100ppm/°C")
        (field (name "RESISTANCE") "10kR")
        (field (name "POWER RATING") "62.5mW")
        (field (name "CASE CODE (IMPERIAL)") "0402")
        (field (name "INTERNAL PART NUMBER") "R000016")
      )
      (libsource (lib "Altium_Lib_Standard") (part "RC0402FR-0710KL"))
    )
    (comp (ref "R16")
      (value "10kR 1%")
      (footprint "RES-SMD-0402-0.4MM-IPC-MED")
      (description "RES 10K 1% 1/16W SMD 0402 YAEGO")
      (fields
        (field (name "MANUFACTURER") "Yageo")
        (field (name "MANUFACTURER PART NUMBER") "RC0402FR-0710KL")
        (field (name "TOLERANCE") "1%")
        (field (name "TEMPERATURE COEFFICIENT") "100ppm/°C")
        (field (name "RESISTANCE") "10kR")
        (field (name "POWER RATING") "62.5mW")
        (field (name "CASE CODE (IMPERIAL)") "0402")
        (field (name "INTERNAL PART NUMBER") "R000016")
      )
      (libsource (lib "Altium_Lib_Standard") (part "RC0402FR-0710KL"))
    )
    (comp (ref "R17")
      (value "10kR 1%")
      (footprint "RES-SMD-0402-0.4MM-IPC-MED")
      (description "RES 10K 1% 1/16W SMD 0402 YAEGO")
      (fields
        (field (name "MANUFACTURER") "Yageo")
        (field (name "MANUFACTURER PART NUMBER") "RC0402FR-0710KL")
        (field (name "TOLERANCE") "1%")
        (field (name "TEMPERATURE COEFFICIENT") "100ppm/°C")
        (field (name "RESISTANCE") "10kR")
        (field (name "POWER RATING") "62.5mW")
        (field (name "CASE CODE (IMPERIAL)") "0402")
        (field (name "INTERNAL PART NUMBER") "R000016")
      )
      (libsource (lib "Altium_Lib_Standard") (part "RC0402FR-0710KL"))
    )
    (comp (ref "R18")
      (value "10kR 1%")
      (footprint "RES-SMD-0402-0.4MM-IPC-MED")
      (description "RES 10K 1% 1/16W SMD 0402 YAEGO")
      (fields
        (field (name "MANUFACTURER") "Yageo")
        (field (name "MANUFACTURER PART NUMBER") "RC0402FR-0710KL")
        (field (name "TOLERANCE") "1%")
        (field (name "TEMPERATURE COEFFICIENT") "100ppm/°C")
        (field (name "RESISTANCE") "10kR")
        (field (name "POWER RATING") "62.5mW")
        (field (name "CASE CODE (IMPERIAL)") "0402")
        (field (name "INTERNAL PART NUMBER") "R000016")
      )
      (libsource (lib "Altium_Lib_Standard") (part "RC0402FR-0710KL"))
    )
    (comp (ref "R19")
      (value "1.5kR 1%")
      (footprint "RES-SMD-0402-0.4MM-IPC-MED")
      (description "RES 1K5 1% 1/16W SMD 0402 YAEGO")
      (fields
        (field (name "MANUFACTURER") "Yageo")
        (field (name "MANUFACTURER PART NUMBER") "RC0402FR-071K5L")
        (field (name "TEMPERATURE COEFFICIENT") "100ppm/°C")
        (field (name "TOLERANCE") "1%")
        (field (name "RESISTANCE") "1.5kR")
        (field (name "MAX POWER DISSIPATION") "62.5mW")
        (field (name "CASE/PACKAGE") "0402")
        (field (name "INTERNAL PART NUMBER") "R000006")
      )
      (libsource (lib "Altium_Lib_Standard") (part "RC0402FR-071K5L"))
    )
    (comp (ref "R20")
      (value "1.5kR 1%")
      (footprint "RES-SMD-0402-0.4MM-IPC-MED")
      (description "RES 1K5 1% 1/16W SMD 0402 YAEGO")
      (fields
        (field (name "MANUFACTURER") "Yageo")
        (field (name "MANUFACTURER PART NUMBER") "RC0402FR-071K5L")
        (field (name "TEMPERATURE COEFFICIENT") "100ppm/°C")
        (field (name "TOLERANCE") "1%")
        (field (name "RESISTANCE") "1.5kR")
        (field (name "MAX POWER DISSIPATION") "62.5mW")
        (field (name "CASE/PACKAGE") "0402")
        (field (name "INTERNAL PART NUMBER") "R000006")
      )
      (libsource (lib "Altium_Lib_Standard") (part "RC0402FR-071K5L"))
    )
    (comp (ref "R21")
      (value "1.5kR 1%")
      (footprint "RES-SMD-0402-0.4MM-IPC-MED")
      (description "RES 1K5 1% 1/16W SMD 0402 YAEGO")
      (fields
        (field (name "MANUFACTURER") "Yageo")
        (field (name "MANUFACTURER PART NUMBER") "RC0402FR-071K5L")
        (field (name "TEMPERATURE COEFFICIENT") "100ppm/°C")
        (field (name "TOLERANCE") "1%")
        (field (name "RESISTANCE") "1.5kR")
        (field (name "MAX POWER DISSIPATION") "62.5mW")
        (field (name "CASE/PACKAGE") "0402")
        (field (name "INTERNAL PART NUMBER") "R000006")
      )
      (libsource (lib "Altium_Lib_Standard") (part "RC0402FR-071K5L"))
    )
    (comp (ref "R22")
      (value "1.5kR 1%")
      (footprint "RES-SMD-0402-0.4MM-IPC-MED")
      (description "RES 1K5 1% 1/16W SMD 0402 YAEGO")
      (fields
        (field (name "MANUFACTURER") "Yageo")
        (field (name "MANUFACTURER PART NUMBER") "RC0402FR-071K5L")
        (field (name "TEMPERATURE COEFFICIENT") "100ppm/°C")
        (field (name "TOLERANCE") "1%")
        (field (name "RESISTANCE") "1.5kR")
        (field (name "MAX POWER DISSIPATION") "62.5mW")
        (field (name "CASE/PACKAGE") "0402")
        (field (name "INTERNAL PART NUMBER") "R000006")
      )
      (libsource (lib "Altium_Lib_Standard") (part "RC0402FR-071K5L"))
    )
    (comp (ref "R23")
      (value "1.5kR 1%")
      (footprint "RES-SMD-0402-0.4MM-IPC-MED")
      (description "RES 1K5 1% 1/16W SMD 0402 YAEGO")
      (fields
        (field (name "MANUFACTURER") "Yageo")
        (field (name "MANUFACTURER PART NUMBER") "RC0402FR-071K5L")
        (field (name "TEMPERATURE COEFFICIENT") "100ppm/°C")
        (field (name "TOLERANCE") "1%")
        (field (name "RESISTANCE") "1.5kR")
        (field (name "MAX POWER DISSIPATION") "62.5mW")
        (field (name "CASE/PACKAGE") "0402")
        (field (name "INTERNAL PART NUMBER") "R000006")
      )
      (libsource (lib "Altium_Lib_Standard") (part "RC0402FR-071K5L"))
    )
    (comp (ref "R24")
      (value "1.5kR 1%")
      (footprint "RES-SMD-0402-0.4MM-IPC-MED")
      (description "RES 1K5 1% 1/16W SMD 0402 YAEGO")
      (fields
        (field (name "MANUFACTURER") "Yageo")
        (field (name "MANUFACTURER PART NUMBER") "RC0402FR-071K5L")
        (field (name "TEMPERATURE COEFFICIENT") "100ppm/°C")
        (field (name "TOLERANCE") "1%")
        (field (name "RESISTANCE") "1.5kR")
        (field (name "MAX POWER DISSIPATION") "62.5mW")
        (field (name "CASE/PACKAGE") "0402")
        (field (name "INTERNAL PART NUMBER") "R000006")
      )
      (libsource (lib "Altium_Lib_Standard") (part "RC0402FR-071K5L"))
    )
    (comp (ref "R25")
      (value "1.5kR 1%")
      (footprint "RES-SMD-0402-0.4MM-IPC-MED")
      (description "RES 1K5 1% 1/16W SMD 0402 YAEGO")
      (fields
        (field (name "MANUFACTURER") "Yageo")
        (field (name "MANUFACTURER PART NUMBER") "RC0402FR-071K5L")
        (field (name "TEMPERATURE COEFFICIENT") "100ppm/°C")
        (field (name "TOLERANCE") "1%")
        (field (name "RESISTANCE") "1.5kR")
        (field (name "MAX POWER DISSIPATION") "62.5mW")
        (field (name "CASE/PACKAGE") "0402")
        (field (name "INTERNAL PART NUMBER") "R000006")
      )
      (libsource (lib "Altium_Lib_Standard") (part "RC0402FR-071K5L"))
    )
  )
  (nets
    (net (code "1") (name "/KBM_DATA_0") (class "Default")
      (node (ref "D1") (pin "1") (pinfunction "1_1") (pintype "passive"))
      (node (ref "D10") (pin "1") (pinfunction "1_1") (pintype "passive"))
      (node (ref "D11") (pin "1") (pinfunction "1_1") (pintype "passive"))
      (node (ref "D12") (pin "1") (pinfunction "1_1") (pintype "passive"))
      (node (ref "D13") (pin "1") (pinfunction "1_1") (pintype "passive"))
      (node (ref "D14") (pin "1") (pinfunction "1_1") (pintype "passive"))
      (node (ref "D15") (pin "1") (pinfunction "1_1") (pintype "passive"))
      (node (ref "D16") (pin "1") (pinfunction "1_1") (pintype "passive"))
      (node (ref "D2") (pin "1") (pinfunction "1_1") (pintype "passive"))
      (node (ref "D3") (pin "1") (pinfunction "1_1") (pintype "passive"))
      (node (ref "D4") (pin "1") (pinfunction "1_1") (pintype "passive"))
      (node (ref "D5") (pin "1") (pinfunction "1_1") (pintype "passive"))
      (node (ref "D6") (pin "1") (pinfunction "1_1") (pintype "passive"))
      (node (ref "D7") (pin "1") (pinfunction "1_1") (pintype "passive"))
      (node (ref "D8") (pin "1") (pinfunction "1_1") (pintype "passive"))
      (node (ref "D9") (pin "1") (pinfunction "1_1") (pintype "passive"))
      (node (ref "R19") (pin "1") (pinfunction "1_1") (pintype "passive"))
    )
    (net (code "2") (name "/KBM_DATA_1") (class "Default")
      (node (ref "D17") (pin "1") (pinfunction "1_1") (pintype "passive"))
      (node (ref "D18") (pin "1") (pinfunction "1_1") (pintype "passive"))
      (node (ref "D19") (pin "1") (pinfunction "1_1") (pintype "passive"))
      (node (ref "D20") (pin "1") (pinfunction "1_1") (pintype "passive"))
      (node (ref "D21") (pin "1") (pinfunction "1_1") (pintype "passive"))
      (node (ref "D22") (pin "1") (pinfunction "1_1") (pintype "passive"))
      (node (ref "D23") (pin "1") (pinfunction "1_1") (pintype "passive"))
      (node (ref "D24") (pin "1") (pinfunction "1_1") (pintype "passive"))
      (node (ref "D25") (pin "1") (pinfunction "1_1") (pintype "passive"))
      (node (ref "D26") (pin "1") (pinfunction "1_1") (pintype "passive"))
      (node (ref "D27") (pin "1") (pinfunction "1_1") (pintype "passive"))
      (node (ref "D28") (pin "1") (pinfunction "1_1") (pintype "passive"))
      (node (ref "D29") (pin "1") (pinfunction "1_1") (pintype "passive"))
      (node (ref "D30") (pin "1") (pinfunction "1_1") (pintype "passive"))
      (node (ref "D31") (pin "1") (pinfunction "1_1") (pintype "passive"))
      (node (ref "D32") (pin "1") (pinfunction "1_1") (pintype "passive"))
      (node (ref "R20") (pin "1") (pinfunction "1_1") (pintype "passive"))
    )
    (net (code "3") (name "/KBM_DATA_2") (class "Default")
      (node (ref "D33") (pin "1") (pinfunction "1_1") (pintype "passive"))
      (node (ref "D34") (pin "1") (pinfunction "1_1") (pintype "passive"))
      (node (ref "D35") (pin "1") (pinfunction "1_1") (pintype "passive"))
      (node (ref "D36") (pin "1") (pinfunction "1_1") (pintype "passive"))
      (node (ref "D37") (pin "1") (pinfunction "1_1") (pintype "passive"))
      (node (ref "D38") (pin "1") (pinfunction "1_1") (pintype "passive"))
      (node (ref "D39") (pin "1") (pinfunction "1_1") (pintype "passive"))
      (node (ref "D40") (pin "1") (pinfunction "1_1") (pintype "passive"))
      (node (ref "D41") (pin "1") (pinfunction "1_1") (pintype "passive"))
      (node (ref "D42") (pin "1") (pinfunction "1_1") (pintype "passive"))
      (node (ref "D43") (pin "1") (pinfunction "1_1") (pintype "passive"))
      (node (ref "D44") (pin "1") (pinfunction "1_1") (pintype "passive"))
      (node (ref "D45") (pin "1") (pinfunction "1_1") (pintype "passive"))
      (node (ref "D46") (pin "1") (pinfunction "1_1") (pintype "passive"))
      (node (ref "D47") (pin "1") (pinfunction "1_1") (pintype "passive"))
      (node (ref "R21") (pin "1") (pinfunction "1_1") (pintype "passive"))
    )
    (net (code "4") (name "/KBM_DATA_3") (class "Default")
      (node (ref "D48") (pin "1") (pinfunction "1_1") (pintype "passive"))
      (node (ref "D49") (pin "1") (pinfunction "1_1") (pintype "passive"))
      (node (ref "D50") (pin "1") (pinfunction "1_1") (pintype "passive"))
      (node (ref "D51") (pin "1") (pinfunction "1_1") (pintype "passive"))
      (node (ref "D52") (pin "1") (pinfunction "1_1") (pintype "passive"))
      (node (ref "D53") (pin "1") (pinfunction "1_1") (pintype "passive"))
      (node (ref "D54") (pin "1") (pinfunction "1_1") (pintype "passive"))
      (node (ref "D55") (pin "1") (pinfunction "1_1") (pintype "passive"))
      (node (ref "D56") (pin "1") (pinfunction "1_1") (pintype "passive"))
      (node (ref "D57") (pin "1") (pinfunction "1_1") (pintype "passive"))
      (node (ref "D58") (pin "1") (pinfunction "1_1") (pintype "passive"))
      (node (ref "D59") (pin "1") (pinfunction "1_1") (pintype "passive"))
      (node (ref "D60") (pin "1") (pinfunction "1_1") (pintype "passive"))
      (node (ref "D61") (pin "1") (pinfunction "1_1") (pintype "passive"))
      (node (ref "D62") (pin "1") (pinfunction "1_1") (pintype "passive"))
      (node (ref "R22") (pin "1") (pinfunction "1_1") (pintype "passive"))
    )
    (net (code "5") (name "/KBM_DATA_4") (class "Default")
      (node (ref "D63") (pin "1") (pinfunction "1_1") (pintype "passive"))
      (node (ref "D64") (pin "1") (pinfunction "1_1") (pintype "passive"))
      (node (ref "D65") (pin "1") (pinfunction "1_1") (pintype "passive"))
      (node (ref "D66") (pin "1") (pinfunction "1_1") (pintype "passive"))
      (node (ref "D67") (pin "1") (pinfunction "1_1") (pintype "passive"))
      (node (ref "D68") (pin "1") (pinfunction "1_1") (pintype "passive"))
      (node (ref "D69") (pin "1") (pinfunction "1_1") (pintype "passive"))
      (node (ref "D70") (pin "1") (pinfunction "1_1") (pintype "passive"))
      (node (ref "D71") (pin "1") (pinfunction "1_1") (pintype "passive"))
      (node (ref "D72") (pin "1") (pinfunction "1_1") (pintype "passive"))
      (node (ref "D73") (pin "1") (pinfunction "1_1") (pintype "passive"))
      (node (ref "D74") (pin "1") (pinfunction "1_1") (pintype "passive"))
      (node (ref "D75") (pin "1") (pinfunction "1_1") (pintype "passive"))
      (node (ref "D76") (pin "1") (pinfunction "1_1") (pintype "passive"))
      (node (ref "R23") (pin "1") (pinfunction "1_1") (pintype "passive"))
    )
    (net (code "6") (name "/KBM_DATA_5") (class "Default")
      (node (ref "D77") (pin "1") (pinfunction "1_1") (pintype "passive"))
      (node (ref "D78") (pin "1") (pinfunction "1_1") (pintype "passive"))
      (node (ref "D79") (pin "1") (pinfunction "1_1") (pintype "passive"))
      (node (ref "D80") (pin "1") (pinfunction "1_1") (pintype "passive"))
      (node (ref "D81") (pin "1") (pinfunction "1_1") (pintype "passive"))
      (node (ref "D82") (pin "1") (pinfunction "1_1") (pintype "passive"))
      (node (ref "D83") (pin "1") (pinfunction "1_1") (pintype "passive"))
      (node (ref "D84") (pin "1") (pinfunction "1_1") (pintype "passive"))
      (node (ref "D85") (pin "1") (pinfunction "1_1") (pintype "passive"))
      (node (ref "D86") (pin "1") (pinfunction "1_1") (pintype "passive"))
      (node (ref "D87") (pin "1") (pinfunction "1_1") (pintype "passive"))
      (node (ref "D88") (pin "1") (pinfunction "1_1") (pintype "passive"))
      (node (ref "D89") (pin "1") (pinfunction "1_1") (pintype "passive"))
      (node (ref "D90") (pin "1") (pinfunction "1_1") (pintype "passive"))
      (node (ref "R24") (pin "1") (pinfunction "1_1") (pintype "passive"))
    )
    (net (code "7") (name "/KBM_DATA_6") (class "Default")
      (node (ref "D91") (pin "1") (pinfunction "1_1") (pintype "passive"))
      (node (ref "D92") (pin "1") (pinfunction "1_1") (pintype "passive"))
      (node (ref "D93") (pin "1") (pinfunction "1_1") (pintype "passive"))
      (node (ref "D94") (pin "1") (pinfunction "1_1") (pintype "passive"))
      (node (ref "D95") (pin "1") (pinfunction "1_1") (pintype "passive"))
      (node (ref "D96") (pin "1") (pinfunction "1_1") (pintype "passive"))
      (node (ref "D97") (pin "1") (pinfunction "1_1") (pintype "passive"))
      (node (ref "D98") (pin "1") (pinfunction "1_1") (pintype "passive"))
      (node (ref "D99") (pin "1") (pinfunction "1_1") (pintype "passive"))
      (node (ref "R25") (pin "1") (pinfunction "1_1") (pintype "passive"))
    )
    (net (code "8") (name "/KBM_PROBE_0") (class "Default")
      (node (ref "BTN18") (pin "2") (pinfunction "2_2") (pintype "passive"))
      (node (ref "BTN2") (pin "2") (pinfunction "2_2") (pintype "passive"))
      (node (ref "BTN34") (pin "2") (pinfunction "2_2") (pintype "passive"))
      (node (ref "BTN49") (pin "2") (pinfunction "2_2") (pintype "passive"))
      (node (ref "BTN64") (pin "2") (pinfunction "2_2") (pintype "passive"))
      (node (ref "BTN78") (pin "2") (pinfunction "2_2") (pintype "passive"))
      (node (ref "BTN92") (pin "2") (pinfunction "2_2") (pintype "passive"))
      (node (ref "R3") (pin "2") (pinfunction "2_2") (pintype "passive"))
    )
    (net (code "9") (name "/KBM_PROBE_1") (class "Default")
      (node (ref "BTN19") (pin "2") (pinfunction "2_2") (pintype "passive"))
      (node (ref "BTN3") (pin "2") (pinfunction "2_2") (pintype "passive"))
      (node (ref "BTN35") (pin "2") (pinfunction "2_2") (pintype "passive"))
      (node (ref "BTN50") (pin "2") (pinfunction "2_2") (pintype "passive"))
      (node (ref "BTN65") (pin "2") (pinfunction "2_2") (pintype "passive"))
      (node (ref "BTN79") (pin "2") (pinfunction "2_2") (pintype "passive"))
      (node (ref "BTN93") (pin "2") (pinfunction "2_2") (pintype "passive"))
      (node (ref "R4") (pin "2") (pinfunction "2_2") (pintype "passive"))
    )
    (net (code "10") (name "/KBM_PROBE_2") (class "Default")
      (node (ref "BTN20") (pin "2") (pinfunction "2_2") (pintype "passive"))
      (node (ref "BTN36") (pin "2") (pinfunction "2_2") (pintype "passive"))
      (node (ref "BTN4") (pin "2") (pinfunction "2_2") (pintype "passive"))
      (node (ref "BTN51") (pin "2") (pinfunction "2_2") (pintype "passive"))
      (node (ref "BTN66") (pin "2") (pinfunction "2_2") (pintype "passive"))
      (node (ref "BTN80") (pin "2") (pinfunction "2_2") (pintype "passive"))
      (node (ref "BTN94") (pin "2") (pinfunction "2_2") (pintype "passive"))
      (node (ref "R5") (pin "2") (pinfunction "2_2") (pintype "passive"))
    )
    (net (code "11") (name "/KBM_PROBE_3") (class "Default")
      (node (ref "BTN21") (pin "2") (pinfunction "2_2") (pintype "passive"))
      (node (ref "BTN37") (pin "2") (pinfunction "2_2") (pintype "passive"))
      (node (ref "BTN5") (pin "2") (pinfunction "2_2") (pintype "passive"))
      (node (ref "BTN52") (pin "2") (pinfunction "2_2") (pintype "passive"))
      (node (ref "BTN67") (pin "2") (pinfunction "2_2") (pintype "passive"))
      (node (ref "BTN81") (pin "2") (pinfunction "2_2") (pintype "passive"))
      (node (ref "BTN95") (pin "2") (pinfunction "2_2") (pintype "passive"))
      (node (ref "R6") (pin "2") (pinfunction "2_2") (pintype "passive"))
    )
    (net (code "12") (name "/KBM_PROBE_4") (class "Default")
      (node (ref "BTN22") (pin "2") (pinfunction "2_2") (pintype "passive"))
      (node (ref "BTN38") (pin "2") (pinfunction "2_2") (pintype "passive"))
      (node (ref "BTN53") (pin "2") (pinfunction "2_2") (pintype "passive"))
      (node (ref "BTN6") (pin "2") (pinfunction "2_2") (pintype "passive"))
      (node (ref "BTN68") (pin "2") (pinfunction "2_2") (pintype "passive"))
      (node (ref "BTN82") (pin "2") (pinfunction "2_2") (pintype "passive"))
      (node (ref "R7") (pin "2") (pinfunction "2_2") (pintype "passive"))
    )
    (net (code "13") (name "/KBM_PROBE_5") (class "Default")
      (node (ref "BTN23") (pin "2") (pinfunction "2_2") (pintype "passive"))
      (node (ref "BTN39") (pin "2") (pinfunction "2_2") (pintype "passive"))
      (node (ref "BTN54") (pin "2") (pinfunction "2_2") (pintype "passive"))
      (node (ref "BTN69") (pin "2") (pinfunction "2_2") (pintype "passive"))
      (node (ref "BTN7") (pin "2") (pinfunction "2_2") (pintype "passive"))
      (node (ref "BTN83") (pin "2") (pinfunction "2_2") (pintype "passive"))
      (node (ref "R8") (pin "2") (pinfunction "2_2") (pintype "passive"))
    )
    (net (code "14") (name "/KBM_PROBE_6") (class "Default")
      (node (ref "BTN24") (pin "2") (pinfunction "2_2") (pintype "passive"))
      (node (ref "BTN40") (pin "2") (pinfunction "2_2") (pintype "passive"))
      (node (ref "BTN55") (pin "2") (pinfunction "2_2") (pintype "passive"))
      (node (ref "BTN70") (pin "2") (pinfunction "2_2") (pintype "passive"))
      (node (ref "BTN8") (pin "2") (pinfunction "2_2") (pintype "passive"))
      (node (ref "BTN84") (pin "2") (pinfunction "2_2") (pintype "passive"))
      (node (ref "R9") (pin "2") (pinfunction "2_2") (pintype "passive"))
    )
    (net (code "15") (name "/KBM_PROBE_7") (class "Default")
      (node (ref "BTN25") (pin "2") (pinfunction "2_2") (pintype "passive"))
      (node (ref "BTN41") (pin "2") (pinfunction "2_2") (pintype "passive"))
      (node (ref "BTN56") (pin "2") (pinfunction "2_2") (pintype "passive"))
      (node (ref "BTN71") (pin "2") (pinfunction "2_2") (pintype "passive"))
      (node (ref "BTN85") (pin "2") (pinfunction "2_2") (pintype "passive"))
      (node (ref "BTN9") (pin "2") (pinfunction "2_2") (pintype "passive"))
      (node (ref "BTN96") (pin "2") (pinfunction "2_2") (pintype "passive"))
      (node (ref "R10") (pin "2") (pinfunction "2_2") (pintype "passive"))
    )
    (net (code "16") (name "/KBM_PROBE_8") (class "Default")
      (node (ref "BTN10") (pin "2") (pinfunction "2_2") (pintype "passive"))
      (node (ref "BTN26") (pin "2") (pinfunction "2_2") (pintype "passive"))
      (node (ref "BTN42") (pin "2") (pinfunction "2_2") (pintype "passive"))
      (node (ref "BTN57") (pin "2") (pinfunction "2_2") (pintype "passive"))
      (node (ref "BTN72") (pin "2") (pinfunction "2_2") (pintype "passive"))
      (node (ref "BTN86") (pin "2") (pinfunction "2_2") (pintype "passive"))
      (node (ref "R11") (pin "2") (pinfunction "2_2") (pintype "passive"))
    )
    (net (code "17") (name "/KBM_PROBE_9") (class "Default")
      (node (ref "BTN11") (pin "2") (pinfunction "2_2") (pintype "passive"))
      (node (ref "BTN27") (pin "2") (pinfunction "2_2") (pintype "passive"))
      (node (ref "BTN43") (pin "2") (pinfunction "2_2") (pintype "passive"))
      (node (ref "BTN58") (pin "2") (pinfunction "2_2") (pintype "passive"))
      (node (ref "BTN73") (pin "2") (pinfunction "2_2") (pintype "passive"))
      (node (ref "BTN87") (pin "2") (pinfunction "2_2") (pintype "passive"))
      (node (ref "R12") (pin "2") (pinfunction "2_2") (pintype "passive"))
    )
    (net (code "18") (name "/KBM_PROBE_10") (class "Default")
      (node (ref "BTN12") (pin "2") (pinfunction "2_2") (pintype "passive"))
      (node (ref "BTN28") (pin "2") (pinfunction "2_2") (pintype "passive"))
      (node (ref "BTN44") (pin "2") (pinfunction "2_2") (pintype "passive"))
      (node (ref "BTN59") (pin "2") (pinfunction "2_2") (pintype "passive"))
      (node (ref "BTN74") (pin "2") (pinfunction "2_2") (pintype "passive"))
      (node (ref "BTN88") (pin "2") (pinfunction "2_2") (pintype "passive"))
      (node (ref "R13") (pin "2") (pinfunction "2_2") (pintype "passive"))
    )
    (net (code "19") (name "/KBM_PROBE_11") (class "Default")
      (node (ref "BTN13") (pin "2") (pinfunction "2_2") (pintype "passive"))
      (node (ref "BTN29") (pin "2") (pinfunction "2_2") (pintype "passive"))
      (node (ref "BTN45") (pin "2") (pinfunction "2_2") (pintype "passive"))
      (node (ref "BTN60") (pin "2") (pinfunction "2_2") (pintype "passive"))
      (node (ref "BTN75") (pin "2") (pinfunction "2_2") (pintype "passive"))
      (node (ref "BTN89") (pin "2") (pinfunction "2_2") (pintype "passive"))
      (node (ref "BTN97") (pin "2") (pinfunction "2_2") (pintype "passive"))
      (node (ref "R14") (pin "2") (pinfunction "2_2") (pintype "passive"))
    )
    (net (code "20") (name "/KBM_PROBE_12") (class "Default")
      (node (ref "BTN14") (pin "2") (pinfunction "2_2") (pintype "passive"))
      (node (ref "BTN30") (pin "2") (pinfunction "2_2") (pintype "passive"))
      (node (ref "BTN46") (pin "2") (pinfunction "2_2") (pintype "passive"))
      (node (ref "BTN61") (pin "2") (pinfunction "2_2") (pintype "passive"))
      (node (ref "BTN76") (pin "2") (pinfunction "2_2") (pintype "passive"))
      (node (ref "BTN90") (pin "2") (pinfunction "2_2") (pintype "passive"))
      (node (ref "BTN98") (pin "2") (pinfunction "2_2") (pintype "passive"))
      (node (ref "R15") (pin "2") (pinfunction "2_2") (pintype "passive"))
    )
    (net (code "21") (name "/KBM_PROBE_13") (class "Default")
      (node (ref "BTN15") (pin "2") (pinfunction "2_2") (pintype "passive"))
      (node (ref "BTN31") (pin "2") (pinfunction "2_2") (pintype "passive"))
      (node (ref "BTN47") (pin "2") (pinfunction "2_2") (pintype "passive"))
      (node (ref "BTN62") (pin "2") (pinfunction "2_2") (pintype "passive"))
      (node (ref "BTN77") (pin "2") (pinfunction "2_2") (pintype "passive"))
      (node (ref "BTN99") (pin "2") (pinfunction "2_2") (pintype "passive"))
      (node (ref "R16") (pin "2") (pinfunction "2_2") (pintype "passive"))
    )
    (net (code "22") (name "/KBM_PROBE_14") (class "Default")
      (node (ref "BTN100") (pin "2") (pinfunction "2_2") (pintype "passive"))
      (node (ref "BTN16") (pin "2") (pinfunction "2_2") (pintype "passive"))
      (node (ref "BTN32") (pin "2") (pinfunction "2_2") (pintype "passive"))
      (node (ref "BTN48") (pin "2") (pinfunction "2_2") (pintype "passive"))
      (node (ref "BTN63") (pin "2") (pinfunction "2_2") (pintype "passive"))
      (node (ref "BTN91") (pin "2") (pinfunction "2_2") (pintype "passive"))
      (node (ref "R17") (pin "2") (pinfunction "2_2") (pintype "passive"))
    )
    (net (code "23") (name "/KBM_PROBE_15") (class "Default")
      (node (ref "BTN17") (pin "2") (pinfunction "2_2") (pintype "passive"))
      (node (ref "BTN33") (pin "2") (pinfunction "2_2") (pintype "passive"))
      (node (ref "R18") (pin "2") (pinfunction "2_2") (pintype "passive"))
    )
    (net (code "24") (name "GND") (class "Default")
      (node (ref "R10") (pin "1") (pinfunction "1_1") (pintype "passive"))
      (node (ref "R11") (pin "1") (pinfunction "1_1") (pintype "passive"))
      (node (ref "R12") (pin "1") (pinfunction "1_1") (pintype "passive"))
      (node (ref "R13") (pin "1") (pinfunction "1_1") (pintype "passive"))
      (node (ref "R14") (pin "1") (pinfunction "1_1") (pintype "passive"))
      (node (ref "R15") (pin "1") (pinfunction "1_1") (pintype "passive"))
      (node (ref "R16") (pin "1") (pinfunction "1_1") (pintype "passive"))
      (node (ref "R17") (pin "1") (pinfunction "1_1") (pintype "passive"))
      (node (ref "R18") (pin "1") (pinfunction "1_1") (pintype "passive"))
      (node (ref "R19") (pin "2") (pinfunction "2_2") (pintype "passive"))
      (node (ref "R20") (pin "2") (pinfunction "2_2") (pintype "passive"))
      (node (ref "R21") (pin "2") (pinfunction "2_2") (pintype "passive"))
      (node (ref "R22") (pin "2") (pinfunction "2_2") (pintype "passive"))
      (node (ref "R23") (pin "2") (pinfunction "2_2") (pintype "passive"))
      (node (ref "R24") (pin "2") (pinfunction "2_2") (pintype "passive"))
      (node (ref "R25") (pin "2") (pinfunction "2_2") (pintype "passive"))
      (node (ref "R3") (pin "1") (pinfunction "1_1") (pintype "passive"))
      (node (ref "R4") (pin "1") (pinfunction "1_1") (pintype "passive"))
      (node (ref "R5") (pin "1") (pinfunction "1_1") (pintype "passive"))
      (node (ref "R6") (pin "1") (pinfunction "1_1") (pintype "passive"))
      (node (ref "R7") (pin "1") (pinfunction "1_1") (pintype "passive"))
      (node (ref "R8") (pin "1") (pinfunction "1_1") (pintype "passive"))
      (node (ref "R9") (pin "1") (pinfunction "1_1") (pintype "passive"))
    )
    (net (code "25") (name "Net-(BTN2-Pad1)") (class "Default")
      (node (ref "BTN2") (pin "1") (pinfunction "1_1") (pintype "passive"))
      (node (ref "D1") (pin "2") (pinfunction "2_2") (pintype "passive"))
    )
    (net (code "26") (name "Net-(BTN3-Pad1)") (class "Default")
      (node (ref "BTN3") (pin "1") (pinfunction "1_1") (pintype "passive"))
      (node (ref "D2") (pin "2") (pinfunction "2_2") (pintype "passive"))
    )
    (net (code "27") (name "Net-(BTN4-Pad1)") (class "Default")
      (node (ref "BTN4") (pin "1") (pinfunction "1_1") (pintype "passive"))
      (node (ref "D3") (pin "2") (pinfunction "2_2") (pintype "passive"))
    )
    (net (code "28") (name "Net-(BTN5-Pad1)") (class "Default")
      (node (ref "BTN5") (pin "1") (pinfunction "1_1") (pintype "passive"))
      (node (ref "D4") (pin "2") (pinfunction "2_2") (pintype "passive"))
    )
    (net (code "29") (name "Net-(BTN6-Pad1)") (class "Default")
      (node (ref "BTN6") (pin "1") (pinfunction "1_1") (pintype "passive"))
      (node (ref "D5") (pin "2") (pinfunction "2_2") (pintype "passive"))
    )
    (net (code "30") (name "Net-(BTN7-Pad1)") (class "Default")
      (node (ref "BTN7") (pin "1") (pinfunction "1_1") (pintype "passive"))
      (node (ref "D6") (pin "2") (pinfunction "2_2") (pintype "passive"))
    )
    (net (code "31") (name "Net-(BTN8-Pad1)") (class "Default")
      (node (ref "BTN8") (pin "1") (pinfunction "1_1") (pintype "passive"))
      (node (ref "D7") (pin "2") (pinfunction "2_2") (pintype "passive"))
    )
    (net (code "32") (name "Net-(BTN9-Pad1)") (class "Default")
      (node (ref "BTN9") (pin "1") (pinfunction "1_1") (pintype "passive"))
      (node (ref "D8") (pin "2") (pinfunction "2_2") (pintype "passive"))
    )
    (net (code "33") (name "Net-(BTN10-Pad1)") (class "Default")
      (node (ref "BTN10") (pin "1") (pinfunction "1_1") (pintype "passive"))
      (node (ref "D9") (pin "2") (pinfunction "2_2") (pintype "passive"))
    )
    (net (code "34") (name "Net-(BTN11-Pad1)") (class "Default")
      (node (ref "BTN11") (pin "1") (pinfunction "1_1") (pintype "passive"))
      (node (ref "D10") (pin "2") (pinfunction "2_2") (pintype "passive"))
    )
    (net (code "35") (name "Net-(BTN12-Pad1)") (class "Default")
      (node (ref "BTN12") (pin "1") (pinfunction "1_1") (pintype "passive"))
      (node (ref "D11") (pin "2") (pinfunction "2_2") (pintype "passive"))
    )
    (net (code "36") (name "Net-(BTN13-Pad1)") (class "Default")
      (node (ref "BTN13") (pin "1") (pinfunction "1_1") (pintype "passive"))
      (node (ref "D12") (pin "2") (pinfunction "2_2") (pintype "passive"))
    )
    (net (code "37") (name "Net-(BTN14-Pad1)") (class "Default")
      (node (ref "BTN14") (pin "1") (pinfunction "1_1") (pintype "passive"))
      (node (ref "D13") (pin "2") (pinfunction "2_2") (pintype "passive"))
    )
    (net (code "38") (name "Net-(BTN15-Pad1)") (class "Default")
      (node (ref "BTN15") (pin "1") (pinfunction "1_1") (pintype "passive"))
      (node (ref "D14") (pin "2") (pinfunction "2_2") (pintype "passive"))
    )
    (net (code "39") (name "Net-(BTN16-Pad1)") (class "Default")
      (node (ref "BTN16") (pin "1") (pinfunction "1_1") (pintype "passive"))
      (node (ref "D15") (pin "2") (pinfunction "2_2") (pintype "passive"))
    )
    (net (code "40") (name "Net-(BTN17-Pad1)") (class "Default")
      (node (ref "BTN17") (pin "1") (pinfunction "1_1") (pintype "passive"))
      (node (ref "D16") (pin "2") (pinfunction "2_2") (pintype "passive"))
    )
    (net (code "41") (name "Net-(BTN18-Pad1)") (class "Default")
      (node (ref "BTN18") (pin "1") (pinfunction "1_1") (pintype "passive"))
      (node (ref "D17") (pin "2") (pinfunction "2_2") (pintype "passive"))
    )
    (net (code "42") (name "Net-(BTN19-Pad1)") (class "Default")
      (node (ref "BTN19") (pin "1") (pinfunction "1_1") (pintype "passive"))
      (node (ref "D18") (pin "2") (pinfunction "2_2") (pintype "passive"))
    )
    (net (code "43") (name "Net-(BTN20-Pad1)") (class "Default")
      (node (ref "BTN20") (pin "1") (pinfunction "1_1") (pintype "passive"))
      (node (ref "D19") (pin "2") (pinfunction "2_2") (pintype "passive"))
    )
    (net (code "44") (name "Net-(BTN21-Pad1)") (class "Default")
      (node (ref "BTN21") (pin "1") (pinfunction "1_1") (pintype "passive"))
      (node (ref "D20") (pin "2") (pinfunction "2_2") (pintype "passive"))
    )
    (net (code "45") (name "Net-(BTN22-Pad1)") (class "Default")
      (node (ref "BTN22") (pin "1") (pinfunction "1_1") (pintype "passive"))
      (node (ref "D21") (pin "2") (pinfunction "2_2") (pintype "passive"))
    )
    (net (code "46") (name "Net-(BTN23-Pad1)") (class "Default")
      (node (ref "BTN23") (pin "1") (pinfunction "1_1") (pintype "passive"))
      (node (ref "D22") (pin "2") (pinfunction "2_2") (pintype "passive"))
    )
    (net (code "47") (name "Net-(BTN24-Pad1)") (class "Default")
      (node (ref "BTN24") (pin "1") (pinfunction "1_1") (pintype "passive"))
      (node (ref "D23") (pin "2") (pinfunction "2_2") (pintype "passive"))
    )
    (net (code "48") (name "Net-(BTN25-Pad1)") (class "Default")
      (node (ref "BTN25") (pin "1") (pinfunction "1_1") (pintype "passive"))
      (node (ref "D24") (pin "2") (pinfunction "2_2") (pintype "passive"))
    )
    (net (code "49") (name "Net-(BTN26-Pad1)") (class "Default")
      (node (ref "BTN26") (pin "1") (pinfunction "1_1") (pintype "passive"))
      (node (ref "D25") (pin "2") (pinfunction "2_2") (pintype "passive"))
    )
    (net (code "50") (name "Net-(BTN27-Pad1)") (class "Default")
      (node (ref "BTN27") (pin "1") (pinfunction "1_1") (pintype "passive"))
      (node (ref "D26") (pin "2") (pinfunction "2_2") (pintype "passive"))
    )
    (net (code "51") (name "Net-(BTN28-Pad1)") (class "Default")
      (node (ref "BTN28") (pin "1") (pinfunction "1_1") (pintype "passive"))
      (node (ref "D27") (pin "2") (pinfunction "2_2") (pintype "passive"))
    )
    (net (code "52") (name "Net-(BTN29-Pad1)") (class "Default")
      (node (ref "BTN29") (pin "1") (pinfunction "1_1") (pintype "passive"))
      (node (ref "D28") (pin "2") (pinfunction "2_2") (pintype "passive"))
    )
    (net (code "53") (name "Net-(BTN30-Pad1)") (class "Default")
      (node (ref "BTN30") (pin "1") (pinfunction "1_1") (pintype "passive"))
      (node (ref "D29") (pin "2") (pinfunction "2_2") (pintype "passive"))
    )
    (net (code "54") (name "Net-(BTN31-Pad1)") (class "Default")
      (node (ref "BTN31") (pin "1") (pinfunction "1_1") (pintype "passive"))
      (node (ref "D30") (pin "2") (pinfunction "2_2") (pintype "passive"))
    )
    (net (code "55") (name "Net-(BTN32-Pad1)") (class "Default")
      (node (ref "BTN32") (pin "1") (pinfunction "1_1") (pintype "passive"))
      (node (ref "D31") (pin "2") (pinfunction "2_2") (pintype "passive"))
    )
    (net (code "56") (name "Net-(BTN33-Pad1)") (class "Default")
      (node (ref "BTN33") (pin "1") (pinfunction "1_1") (pintype "passive"))
      (node (ref "D32") (pin "2") (pinfunction "2_2") (pintype "passive"))
    )
    (net (code "57") (name "Net-(BTN34-Pad1)") (class "Default")
      (node (ref "BTN34") (pin "1") (pinfunction "1_1") (pintype "passive"))
      (node (ref "D33") (pin "2") (pinfunction "2_2") (pintype "passive"))
    )
    (net (code "58") (name "Net-(BTN35-Pad1)") (class "Default")
      (node (ref "BTN35") (pin "1") (pinfunction "1_1") (pintype "passive"))
      (node (ref "D34") (pin "2") (pinfunction "2_2") (pintype "passive"))
    )
    (net (code "59") (name "Net-(BTN36-Pad1)") (class "Default")
      (node (ref "BTN36") (pin "1") (pinfunction "1_1") (pintype "passive"))
      (node (ref "D35") (pin "2") (pinfunction "2_2") (pintype "passive"))
    )
    (net (code "60") (name "Net-(BTN37-Pad1)") (class "Default")
      (node (ref "BTN37") (pin "1") (pinfunction "1_1") (pintype "passive"))
      (node (ref "D36") (pin "2") (pinfunction "2_2") (pintype "passive"))
    )
    (net (code "61") (name "Net-(BTN38-Pad1)") (class "Default")
      (node (ref "BTN38") (pin "1") (pinfunction "1_1") (pintype "passive"))
      (node (ref "D37") (pin "2") (pinfunction "2_2") (pintype "passive"))
    )
    (net (code "62") (name "Net-(BTN39-Pad1)") (class "Default")
      (node (ref "BTN39") (pin "1") (pinfunction "1_1") (pintype "passive"))
      (node (ref "D38") (pin "2") (pinfunction "2_2") (pintype "passive"))
    )
    (net (code "63") (name "Net-(BTN40-Pad1)") (class "Default")
      (node (ref "BTN40") (pin "1") (pinfunction "1_1") (pintype "passive"))
      (node (ref "D39") (pin "2") (pinfunction "2_2") (pintype "passive"))
    )
    (net (code "64") (name "Net-(BTN41-Pad1)") (class "Default")
      (node (ref "BTN41") (pin "1") (pinfunction "1_1") (pintype "passive"))
      (node (ref "D40") (pin "2") (pinfunction "2_2") (pintype "passive"))
    )
    (net (code "65") (name "Net-(BTN42-Pad1)") (class "Default")
      (node (ref "BTN42") (pin "1") (pinfunction "1_1") (pintype "passive"))
      (node (ref "D41") (pin "2") (pinfunction "2_2") (pintype "passive"))
    )
    (net (code "66") (name "Net-(BTN43-Pad1)") (class "Default")
      (node (ref "BTN43") (pin "1") (pinfunction "1_1") (pintype "passive"))
      (node (ref "D42") (pin "2") (pinfunction "2_2") (pintype "passive"))
    )
    (net (code "67") (name "Net-(BTN44-Pad1)") (class "Default")
      (node (ref "BTN44") (pin "1") (pinfunction "1_1") (pintype "passive"))
      (node (ref "D43") (pin "2") (pinfunction "2_2") (pintype "passive"))
    )
    (net (code "68") (name "Net-(BTN45-Pad1)") (class "Default")
      (node (ref "BTN45") (pin "1") (pinfunction "1_1") (pintype "passive"))
      (node (ref "D44") (pin "2") (pinfunction "2_2") (pintype "passive"))
    )
    (net (code "69") (name "Net-(BTN46-Pad1)") (class "Default")
      (node (ref "BTN46") (pin "1") (pinfunction "1_1") (pintype "passive"))
      (node (ref "D45") (pin "2") (pinfunction "2_2") (pintype "passive"))
    )
    (net (code "70") (name "Net-(BTN47-Pad1)") (class "Default")
      (node (ref "BTN47") (pin "1") (pinfunction "1_1") (pintype "passive"))
      (node (ref "D46") (pin "2") (pinfunction "2_2") (pintype "passive"))
    )
    (net (code "71") (name "Net-(BTN48-Pad1)") (class "Default")
      (node (ref "BTN48") (pin "1") (pinfunction "1_1") (pintype "passive"))
      (node (ref "D47") (pin "2") (pinfunction "2_2") (pintype "passive"))
    )
    (net (code "72") (name "Net-(BTN49-Pad1)") (class "Default")
      (node (ref "BTN49") (pin "1") (pinfunction "1_1") (pintype "passive"))
      (node (ref "D48") (pin "2") (pinfunction "2_2") (pintype "passive"))
    )
    (net (code "73") (name "Net-(BTN50-Pad1)") (class "Default")
      (node (ref "BTN50") (pin "1") (pinfunction "1_1") (pintype "passive"))
      (node (ref "D49") (pin "2") (pinfunction "2_2") (pintype "passive"))
    )
    (net (code "74") (name "Net-(BTN51-Pad1)") (class "Default")
      (node (ref "BTN51") (pin "1") (pinfunction "1_1") (pintype "passive"))
      (node (ref "D50") (pin "2") (pinfunction "2_2") (pintype "passive"))
    )
    (net (code "75") (name "Net-(BTN52-Pad1)") (class "Default")
      (node (ref "BTN52") (pin "1") (pinfunction "1_1") (pintype "passive"))
      (node (ref "D51") (pin "2") (pinfunction "2_2") (pintype "passive"))
    )
    (net (code "76") (name "Net-(BTN53-Pad1)") (class "Default")
      (node (ref "BTN53") (pin "1") (pinfunction "1_1") (pintype "passive"))
      (node (ref "D52") (pin "2") (pinfunction "2_2") (pintype "passive"))
    )
    (net (code "77") (name "Net-(BTN54-Pad1)") (class "Default")
      (node (ref "BTN54") (pin "1") (pinfunction "1_1") (pintype "passive"))
      (node (ref "D53") (pin "2") (pinfunction "2_2") (pintype "passive"))
    )
    (net (code "78") (name "Net-(BTN55-Pad1)") (class "Default")
      (node (ref "BTN55") (pin "1") (pinfunction "1_1") (pintype "passive"))
      (node (ref "D54") (pin "2") (pinfunction "2_2") (pintype "passive"))
    )
    (net (code "79") (name "Net-(BTN56-Pad1)") (class "Default")
      (node (ref "BTN56") (pin "1") (pinfunction "1_1") (pintype "passive"))
      (node (ref "D55") (pin "2") (pinfunction "2_2") (pintype "passive"))
    )
    (net (code "80") (name "Net-(BTN57-Pad1)") (class "Default")
      (node (ref "BTN57") (pin "1") (pinfunction "1_1") (pintype "passive"))
      (node (ref "D56") (pin "2") (pinfunction "2_2") (pintype "passive"))
    )
    (net (code "81") (name "Net-(BTN58-Pad1)") (class "Default")
      (node (ref "BTN58") (pin "1") (pinfunction "1_1") (pintype "passive"))
      (node (ref "D57") (pin "2") (pinfunction "2_2") (pintype "passive"))
    )
    (net (code "82") (name "Net-(BTN59-Pad1)") (class "Default")
      (node (ref "BTN59") (pin "1") (pinfunction "1_1") (pintype "passive"))
      (node (ref "D58") (pin "2") (pinfunction "2_2") (pintype "passive"))
    )
    (net (code "83") (name "Net-(BTN60-Pad1)") (class "Default")
      (node (ref "BTN60") (pin "1") (pinfunction "1_1") (pintype "passive"))
      (node (ref "D59") (pin "2") (pinfunction "2_2") (pintype "passive"))
    )
    (net (code "84") (name "Net-(BTN61-Pad1)") (class "Default")
      (node (ref "BTN61") (pin "1") (pinfunction "1_1") (pintype "passive"))
      (node (ref "D60") (pin "2") (pinfunction "2_2") (pintype "passive"))
    )
    (net (code "85") (name "Net-(BTN62-Pad1)") (class "Default")
      (node (ref "BTN62") (pin "1") (pinfunction "1_1") (pintype "passive"))
      (node (ref "D61") (pin "2") (pinfunction "2_2") (pintype "passive"))
    )
    (net (code "86") (name "Net-(BTN63-Pad1)") (class "Default")
      (node (ref "BTN63") (pin "1") (pinfunction "1_1") (pintype "passive"))
      (node (ref "D62") (pin "2") (pinfunction "2_2") (pintype "passive"))
    )
    (net (code "87") (name "Net-(BTN64-Pad1)") (class "Default")
      (node (ref "BTN64") (pin "1") (pinfunction "1_1") (pintype "passive"))
      (node (ref "D63") (pin "2") (pinfunction "2_2") (pintype "passive"))
    )
    (net (code "88") (name "Net-(BTN65-Pad1)") (class "Default")
      (node (ref "BTN65") (pin "1") (pinfunction "1_1") (pintype "passive"))
      (node (ref "D64") (pin "2") (pinfunction "2_2") (pintype "passive"))
    )
    (net (code "89") (name "Net-(BTN66-Pad1)") (class "Default")
      (node (ref "BTN66") (pin "1") (pinfunction "1_1") (pintype "passive"))
      (node (ref "D65") (pin "2") (pinfunction "2_2") (pintype "passive"))
    )
    (net (code "90") (name "Net-(BTN67-Pad1)") (class "Default")
      (node (ref "BTN67") (pin "1") (pinfunction "1_1") (pintype "passive"))
      (node (ref "D66") (pin "2") (pinfunction "2_2") (pintype "passive"))
    )
    (net (code "91") (name "Net-(BTN68-Pad1)") (class "Default")
      (node (ref "BTN68") (pin "1") (pinfunction "1_1") (pintype "passive"))
      (node (ref "D67") (pin "2") (pinfunction "2_2") (pintype "passive"))
    )
    (net (code "92") (name "Net-(BTN69-Pad1)") (class "Default")
      (node (ref "BTN69") (pin "1") (pinfunction "1_1") (pintype "passive"))
      (node (ref "D68") (pin "2") (pinfunction "2_2") (pintype "passive"))
    )
    (net (code "93") (name "Net-(BTN70-Pad1)") (class "Default")
      (node (ref "BTN70") (pin "1") (pinfunction "1_1") (pintype "passive"))
      (node (ref "D69") (pin "2") (pinfunction "2_2") (pintype "passive"))
    )
    (net (code "94") (name "Net-(BTN71-Pad1)") (class "Default")
      (node (ref "BTN71") (pin "1") (pinfunction "1_1") (pintype "passive"))
      (node (ref "D70") (pin "2") (pinfunction "2_2") (pintype "passive"))
    )
    (net (code "95") (name "Net-(BTN72-Pad1)") (class "Default")
      (node (ref "BTN72") (pin "1") (pinfunction "1_1") (pintype "passive"))
      (node (ref "D71") (pin "2") (pinfunction "2_2") (pintype "passive"))
    )
    (net (code "96") (name "Net-(BTN73-Pad1)") (class "Default")
      (node (ref "BTN73") (pin "1") (pinfunction "1_1") (pintype "passive"))
      (node (ref "D72") (pin "2") (pinfunction "2_2") (pintype "passive"))
    )
    (net (code "97") (name "Net-(BTN74-Pad1)") (class "Default")
      (node (ref "BTN74") (pin "1") (pinfunction "1_1") (pintype "passive"))
      (node (ref "D73") (pin "2") (pinfunction "2_2") (pintype "passive"))
    )
    (net (code "98") (name "Net-(BTN75-Pad1)") (class "Default")
      (node (ref "BTN75") (pin "1") (pinfunction "1_1") (pintype "passive"))
      (node (ref "D74") (pin "2") (pinfunction "2_2") (pintype "passive"))
    )
    (net (code "99") (name "Net-(BTN76-Pad1)") (class "Default")
      (node (ref "BTN76") (pin "1") (pinfunction "1_1") (pintype "passive"))
      (node (ref "D75") (pin "2") (pinfunction "2_2") (pintype "passive"))
    )
    (net (code "100") (name "Net-(BTN77-Pad1)") (class "Default")
      (node (ref "BTN77") (pin "1") (pinfunction "1_1") (pintype "passive"))
      (node (ref "D76") (pin "2") (pinfunction "2_2") (pintype "passive"))
    )
    (net (code "101") (name "Net-(BTN78-Pad1)") (class "Default")
      (node (ref "BTN78") (pin "1") (pinfunction "1_1") (pintype "passive"))
      (node (ref "D77") (pin "2") (pinfunction "2_2") (pintype "passive"))
    )
    (net (code "102") (name "Net-(BTN79-Pad1)") (class "Default")
      (node (ref "BTN79") (pin "1") (pinfunction "1_1") (pintype "passive"))
      (node (ref "D78") (pin "2") (pinfunction "2_2") (pintype "passive"))
    )
    (net (code "103") (name "Net-(BTN80-Pad1)") (class "Default")
      (node (ref "BTN80") (pin "1") (pinfunction "1_1") (pintype "passive"))
      (node (ref "D79") (pin "2") (pinfunction "2_2") (pintype "passive"))
    )
    (net (code "104") (name "Net-(BTN81-Pad1)") (class "Default")
      (node (ref "BTN81") (pin "1") (pinfunction "1_1") (pintype "passive"))
      (node (ref "D80") (pin "2") (pinfunction "2_2") (pintype "passive"))
    )
    (net (code "105") (name "Net-(BTN82-Pad1)") (class "Default")
      (node (ref "BTN82") (pin "1") (pinfunction "1_1") (pintype "passive"))
      (node (ref "D81") (pin "2") (pinfunction "2_2") (pintype "passive"))
    )
    (net (code "106") (name "Net-(BTN83-Pad1)") (class "Default")
      (node (ref "BTN83") (pin "1") (pinfunction "1_1") (pintype "passive"))
      (node (ref "D82") (pin "2") (pinfunction "2_2") (pintype "passive"))
    )
    (net (code "107") (name "Net-(BTN84-Pad1)") (class "Default")
      (node (ref "BTN84") (pin "1") (pinfunction "1_1") (pintype "passive"))
      (node (ref "D83") (pin "2") (pinfunction "2_2") (pintype "passive"))
    )
    (net (code "108") (name "Net-(BTN85-Pad1)") (class "Default")
      (node (ref "BTN85") (pin "1") (pinfunction "1_1") (pintype "passive"))
      (node (ref "D84") (pin "2") (pinfunction "2_2") (pintype "passive"))
    )
    (net (code "109") (name "Net-(BTN86-Pad1)") (class "Default")
      (node (ref "BTN86") (pin "1") (pinfunction "1_1") (pintype "passive"))
      (node (ref "D85") (pin "2") (pinfunction "2_2") (pintype "passive"))
    )
    (net (code "110") (name "Net-(BTN87-Pad1)") (class "Default")
      (node (ref "BTN87") (pin "1") (pinfunction "1_1") (pintype "passive"))
      (node (ref "D86") (pin "2") (pinfunction "2_2") (pintype "passive"))
    )
    (net (code "111") (name "Net-(BTN88-Pad1)") (class "Default")
      (node (ref "BTN88") (pin "1") (pinfunction "1_1") (pintype "passive"))
      (node (ref "D87") (pin "2") (pinfunction "2_2") (pintype "passive"))
    )
    (net (code "112") (name "Net-(BTN89-Pad1)") (class "Default")
      (node (ref "BTN89") (pin "1") (pinfunction "1_1") (pintype "passive"))
      (node (ref "D88") (pin "2") (pinfunction "2_2") (pintype "passive"))
    )
    (net (code "113") (name "Net-(BTN90-Pad1)") (class "Default")
      (node (ref "BTN90") (pin "1") (pinfunction "1_1") (pintype "passive"))
      (node (ref "D89") (pin "2") (pinfunction "2_2") (pintype "passive"))
    )
    (net (code "114") (name "Net-(BTN91-Pad1)") (class "Default")
      (node (ref "BTN91") (pin "1") (pinfunction "1_1") (pintype "passive"))
      (node (ref "D90") (pin "2") (pinfunction "2_2") (pintype "passive"))
    )
    (net (code "115") (name "Net-(BTN92-Pad1)") (class "Default")
      (node (ref "BTN92") (pin "1") (pinfunction "1_1") (pintype "passive"))
      (node (ref "D91") (pin "2") (pinfunction "2_2") (pintype "passive"))
    )
    (net (code "116") (name "Net-(BTN93-Pad1)") (class "Default")
      (node (ref "BTN93") (pin "1") (pinfunction "1_1") (pintype "passive"))
      (node (ref "D92") (pin "2") (pinfunction "2_2") (pintype "passive"))
    )
    (net (code "117") (name "Net-(BTN94-Pad1)") (class "Default")
      (node (ref "BTN94") (pin "1") (pinfunction "1_1") (pintype "passive"))
      (node (ref "D93") (pin "2") (pinfunction "2_2") (pintype "passive"))
    )
    (net (code "118") (name "Net-(BTN95-Pad1)") (class "Default")
      (node (ref "BTN95") (pin "1") (pinfunction "1_1") (pintype "passive"))
      (node (ref "D94") (pin "2") (pinfunction "2_2") (pintype "passive"))
    )
    (net (code "119") (name "Net-(BTN96-Pad1)") (class "Default")
      (node (ref "BTN96") (pin "1") (pinfunction "1_1") (pintype "passive"))
      (node (ref "D95") (pin "2") (pinfunction "2_2") (pintype "passive"))
    )
    (net (code "120") (name "Net-(BTN97-Pad1)") (class "Default")
      (node (ref "BTN97") (pin "1") (pinfunction "1_1") (pintype "passive"))
      (node (ref "D96") (pin "2") (pinfunction "2_2") (pintype "passive"))
    )
    (net (code "121") (name "Net-(BTN98-Pad1)") (class "Default")
      (node (ref "BTN98") (pin "1") (pinfunction "1_1") (pintype "passive"))
      (node (ref "D97") (pin "2") (pinfunction "2_2") (pintype "passive"))
    )
    (net (code "122") (name "Net-(BTN99-Pad1)") (class "Default")
      (node (ref "BTN99") (pin "1") (pinfunction "1_1") (pintype "passive"))
      (node (ref "D98") (pin "2") (pinfunction "2_2") (pintype "passive"))
    )
    (net (code "123") (name "Net-(BTN100-Pad1)") (class "Default")
      (node (ref "BTN100") (pin "1") (pinfunction "1_1") (pintype "passive"))
      (node (ref "D99") (pin "2") (pinfunction "2_2") (pintype "passive"))
    )
  )
)
